# PCB_eLock_G592_J1.net
KiCad netlist of a schematic drawn in EAGLE
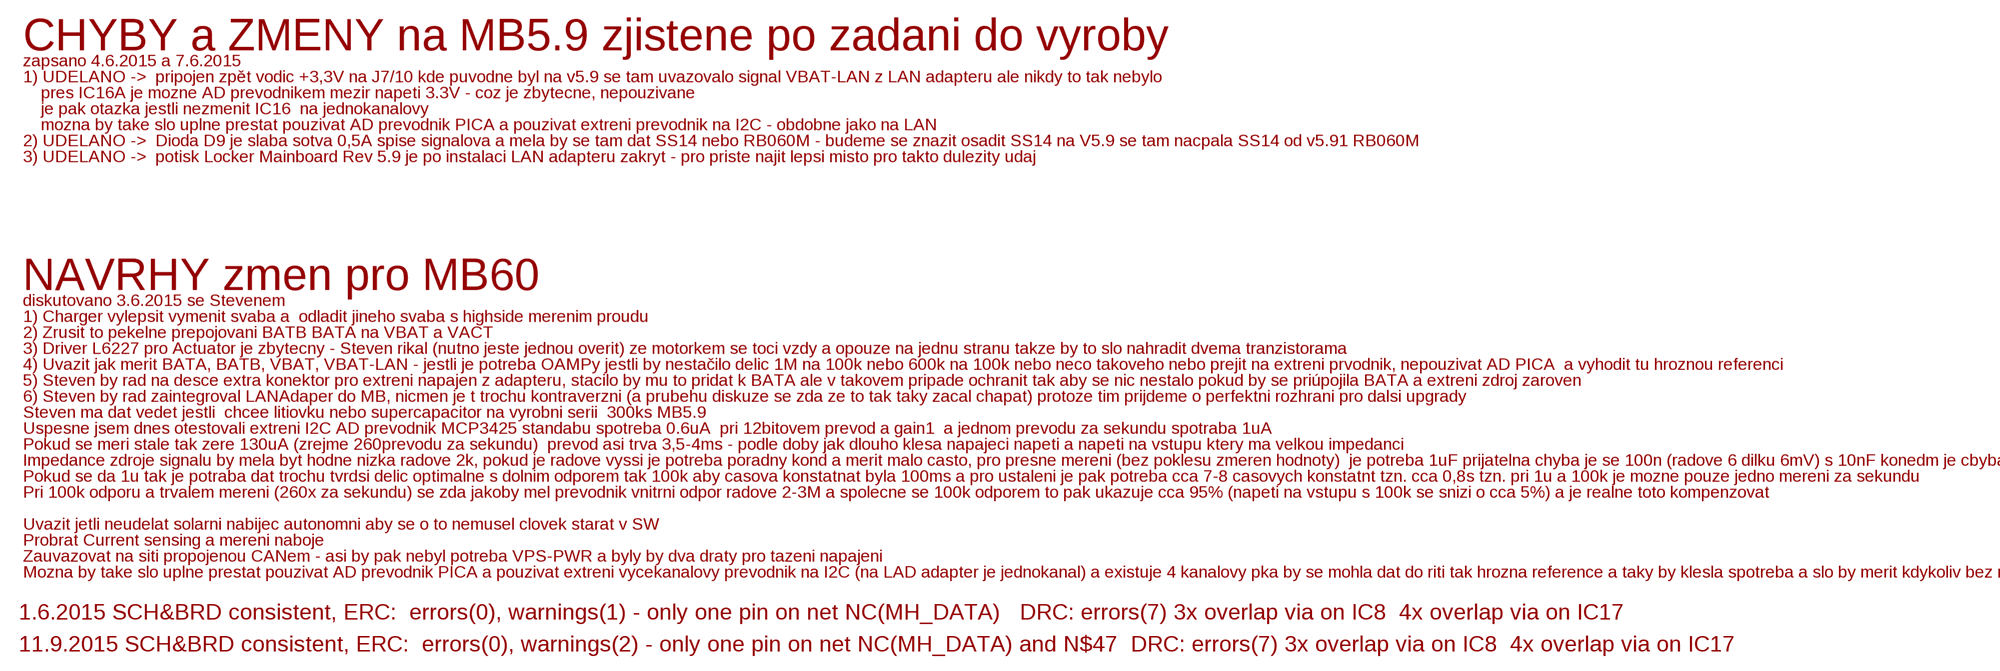
[diagram p0: schematic, sheet 1, part 1 of 3]
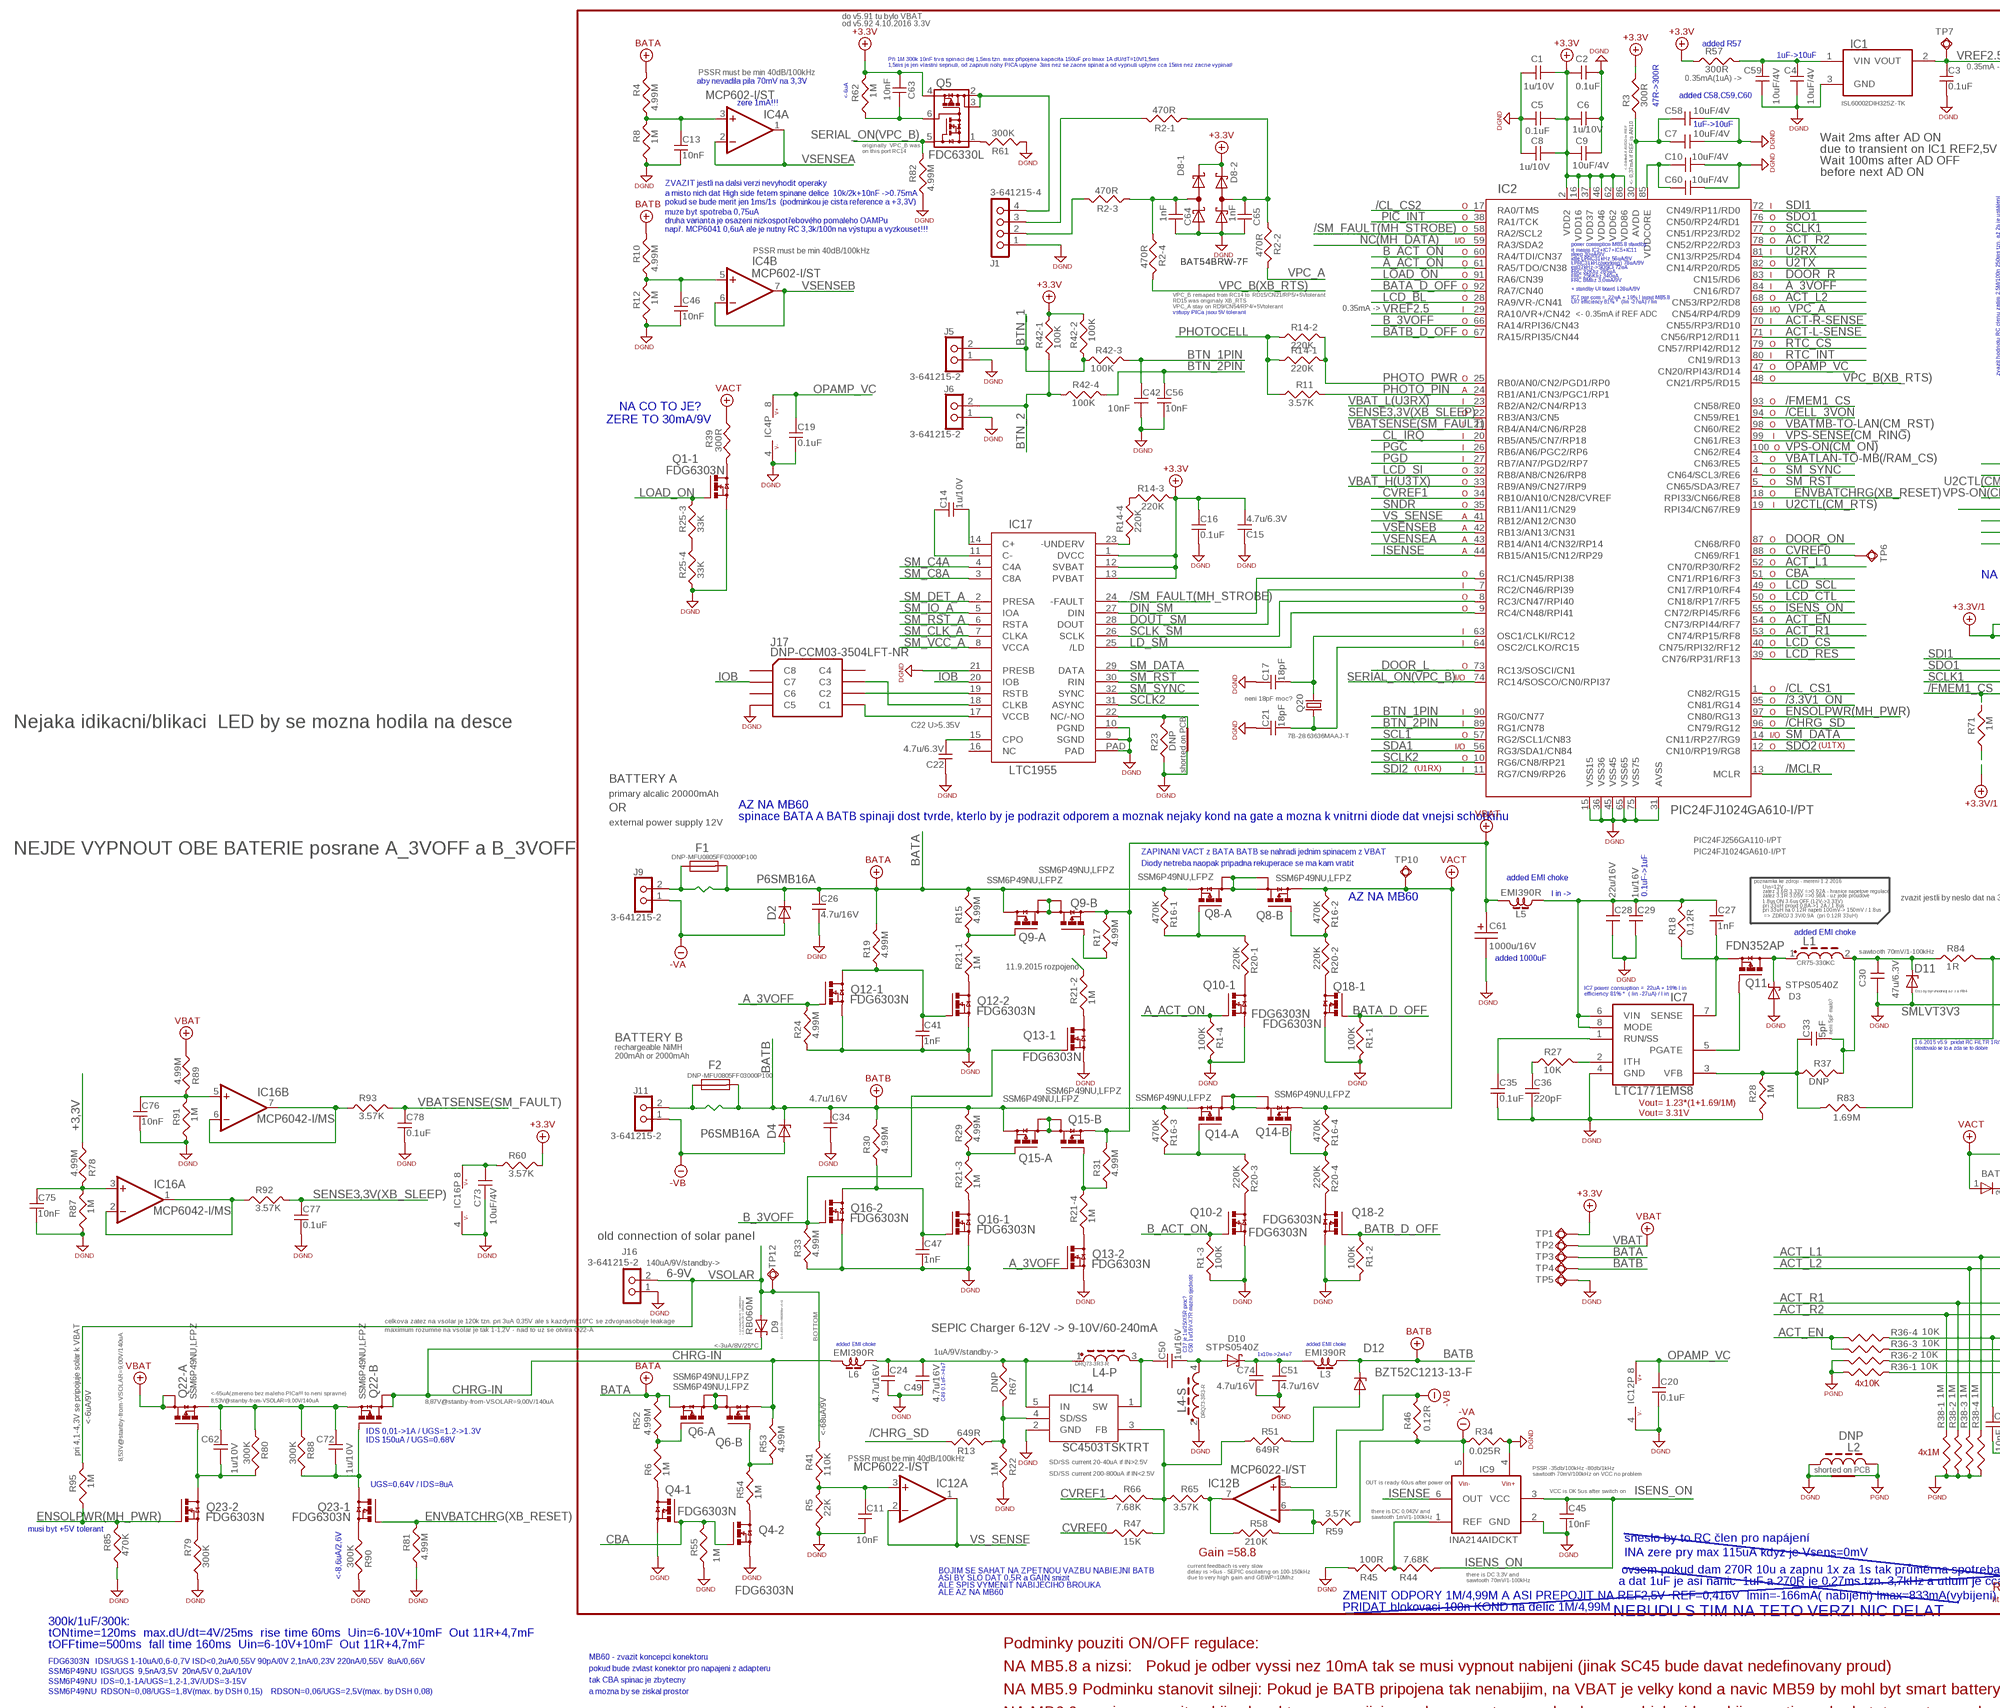
[diagram p1: schematic, sheet 1, part 2 of 3]
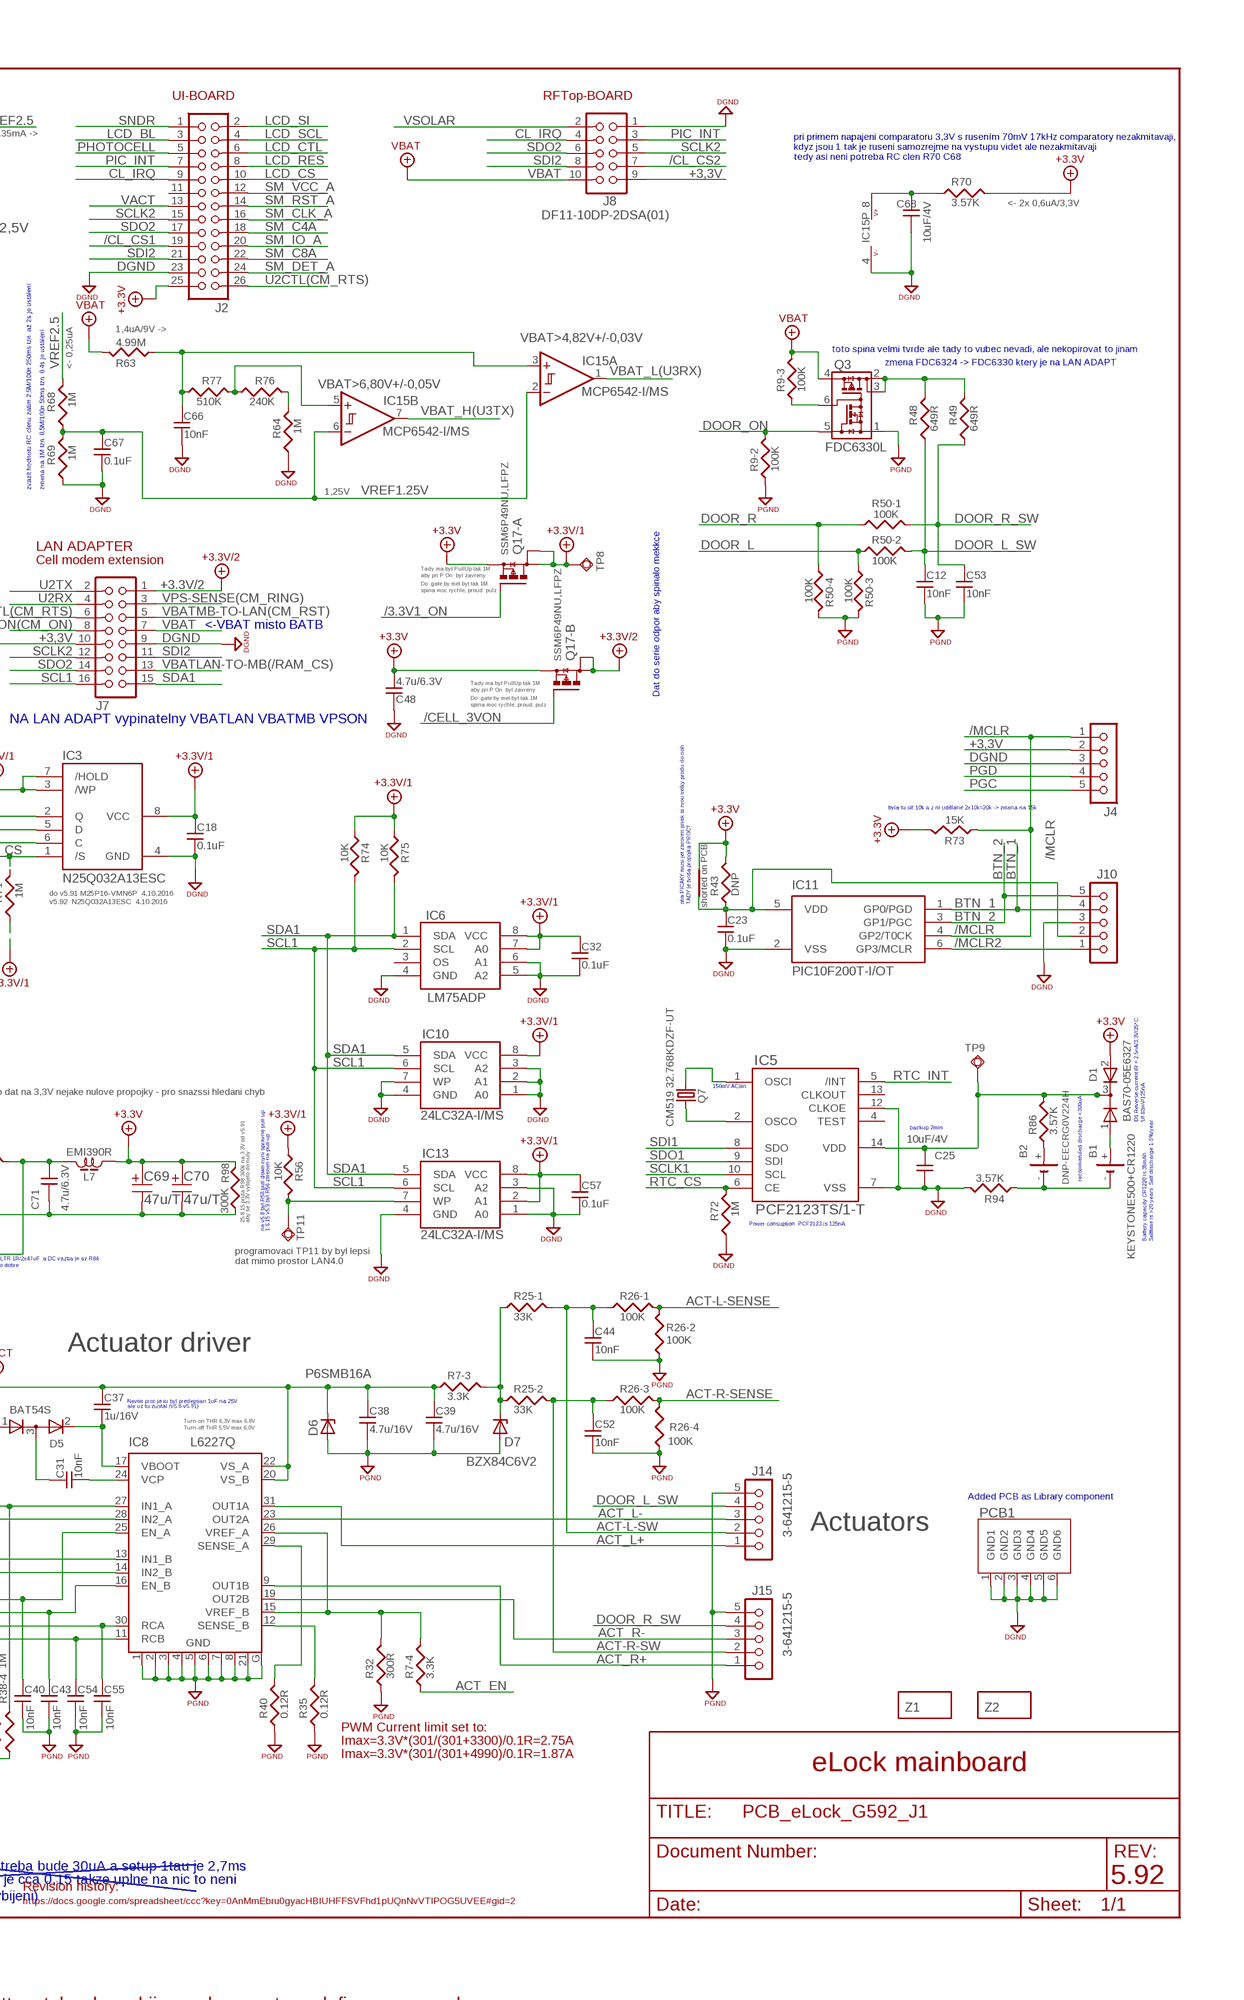
[diagram p2: schematic, sheet 1, part 3 of 3]

(export (version "E")
  (design (tool "Eeschema 10.0.6"))
  (components
    (comp (ref "B1")
      (value "KEYSTONE500+CR1220")
      (footprint "eagle-import:KEYSTONE500")
      (libsource (lib "eagle-import") (part "KEYSTONE500"))
    )
    (comp (ref "B2")
      (value "DNP-EECRG0V224H")
      (footprint "eagle-import:EECRG0V224H")
      (libsource (lib "eagle-import") (part "EECRG0V224H"))
    )
    (comp (ref "C1")
      (value "1u/10V")
      (footprint "eagle-import:0603")
      (libsource (lib "eagle-import") (part "C-0603"))
    )
    (comp (ref "C2")
      (value "0.1uF")
      (footprint "eagle-import:0603")
      (libsource (lib "eagle-import") (part "C-0603"))
    )
    (comp (ref "C3")
      (value "0.1uF")
      (footprint "eagle-import:0603")
      (libsource (lib "eagle-import") (part "C-0603"))
    )
    (comp (ref "C4")
      (value "10uF/4V")
      (footprint "eagle-import:0603")
      (libsource (lib "eagle-import") (part "C-0603"))
    )
    (comp (ref "C5")
      (value "0.1uF")
      (footprint "eagle-import:0603")
      (libsource (lib "eagle-import") (part "C-0603"))
    )
    (comp (ref "C6")
      (value "1u/10V")
      (footprint "eagle-import:0603")
      (libsource (lib "eagle-import") (part "C-0603"))
    )
    (comp (ref "C7")
      (value "10uF/4V")
      (footprint "eagle-import:0603")
      (libsource (lib "eagle-import") (part "C-0603"))
    )
    (comp (ref "C8")
      (value "1u/10V")
      (footprint "eagle-import:0603")
      (libsource (lib "eagle-import") (part "C-0603"))
    )
    (comp (ref "C9")
      (value "10uF/4V")
      (footprint "eagle-import:0603")
      (libsource (lib "eagle-import") (part "C-0603"))
    )
    (comp (ref "C10")
      (value "10uF/4V")
      (footprint "eagle-import:0603")
      (libsource (lib "eagle-import") (part "C-0603"))
    )
    (comp (ref "C11")
      (value "10nF")
      (footprint "eagle-import:0603")
      (libsource (lib "eagle-import") (part "C-0603"))
    )
    (comp (ref "C12")
      (value "10nF")
      (footprint "eagle-import:0603")
      (libsource (lib "eagle-import") (part "C-0603"))
    )
    (comp (ref "C13")
      (value "10nF")
      (footprint "eagle-import:0603")
      (libsource (lib "eagle-import") (part "C-0603"))
    )
    (comp (ref "C14")
      (value "1u/10V")
      (footprint "eagle-import:0603")
      (libsource (lib "eagle-import") (part "C-0603"))
    )
    (comp (ref "C15")
      (value "4.7u/6.3V")
      (footprint "eagle-import:0603")
      (libsource (lib "eagle-import") (part "C-0603"))
    )
    (comp (ref "C16")
      (value "0.1uF")
      (footprint "eagle-import:0603")
      (libsource (lib "eagle-import") (part "C-0603"))
    )
    (comp (ref "C17")
      (value "18pF")
      (footprint "eagle-import:0603")
      (libsource (lib "eagle-import") (part "C-0603"))
    )
    (comp (ref "C18")
      (value "0.1uF")
      (footprint "eagle-import:0603")
      (libsource (lib "eagle-import") (part "C-0603"))
    )
    (comp (ref "C19")
      (value "0.1uF")
      (footprint "eagle-import:0603")
      (libsource (lib "eagle-import") (part "C-0603"))
    )
    (comp (ref "C20")
      (value "0.1uF")
      (footprint "eagle-import:0603")
      (libsource (lib "eagle-import") (part "C-0603"))
    )
    (comp (ref "C21")
      (value "18pF")
      (footprint "eagle-import:0603")
      (libsource (lib "eagle-import") (part "C-0603"))
    )
    (comp (ref "C22")
      (value "4.7u/6.3V")
      (footprint "eagle-import:0603")
      (libsource (lib "eagle-import") (part "C-0603"))
    )
    (comp (ref "C23")
      (value "0.1uF")
      (footprint "eagle-import:0603")
      (libsource (lib "eagle-import") (part "C-0603"))
    )
    (comp (ref "C24")
      (value "4.7u/16V")
      (footprint "eagle-import:0805")
      (libsource (lib "eagle-import") (part "C-0805"))
    )
    (comp (ref "C25")
      (value "10uF/4V")
      (footprint "eagle-import:0603")
      (libsource (lib "eagle-import") (part "C-0603"))
    )
    (comp (ref "C26")
      (value "4.7u/16V")
      (footprint "eagle-import:0805")
      (libsource (lib "eagle-import") (part "C-0805"))
    )
    (comp (ref "C27")
      (value "1nF")
      (footprint "eagle-import:0603")
      (libsource (lib "eagle-import") (part "C-0603"))
    )
    (comp (ref "C28")
      (value "22u/16V")
      (footprint "eagle-import:1210")
      (libsource (lib "eagle-import") (part "C-1210"))
    )
    (comp (ref "C29")
      (value "1u/16V")
      (footprint "eagle-import:0603")
      (libsource (lib "eagle-import") (part "C-0603"))
    )
    (comp (ref "C30")
      (value "47u/6.3V")
      (footprint "eagle-import:1210")
      (libsource (lib "eagle-import") (part "C-1210"))
    )
    (comp (ref "C31")
      (value "10nF")
      (footprint "eagle-import:0603")
      (libsource (lib "eagle-import") (part "C-0603"))
    )
    (comp (ref "C32")
      (value "0.1uF")
      (footprint "eagle-import:0603")
      (libsource (lib "eagle-import") (part "C-0603"))
    )
    (comp (ref "C33")
      (value "5pF")
      (footprint "eagle-import:0603")
      (libsource (lib "eagle-import") (part "C-0603"))
    )
    (comp (ref "C34")
      (value "4.7u/16V")
      (footprint "eagle-import:0805")
      (libsource (lib "eagle-import") (part "C-0805"))
    )
    (comp (ref "C35")
      (value "0.1uF")
      (footprint "eagle-import:0603")
      (libsource (lib "eagle-import") (part "C-0603"))
    )
    (comp (ref "C36")
      (value "220pF")
      (footprint "eagle-import:0603")
      (libsource (lib "eagle-import") (part "C-0603"))
    )
    (comp (ref "C37")
      (value "1u/16V")
      (footprint "eagle-import:0603")
      (libsource (lib "eagle-import") (part "C-0603"))
    )
    (comp (ref "C38")
      (value "4.7u/16V")
      (footprint "eagle-import:0805")
      (libsource (lib "eagle-import") (part "C-0805"))
    )
    (comp (ref "C39")
      (value "4.7u/16V")
      (footprint "eagle-import:0805")
      (libsource (lib "eagle-import") (part "C-0805"))
    )
    (comp (ref "C40")
      (value "10nF")
      (footprint "eagle-import:0603")
      (libsource (lib "eagle-import") (part "C-0603"))
    )
    (comp (ref "C41")
      (value "1nF")
      (footprint "eagle-import:0603")
      (libsource (lib "eagle-import") (part "C-0603"))
    )
    (comp (ref "C42")
      (value "10nF")
      (footprint "eagle-import:0603")
      (libsource (lib "eagle-import") (part "C-0603"))
    )
    (comp (ref "C43")
      (value "10nF")
      (footprint "eagle-import:0603")
      (libsource (lib "eagle-import") (part "C-0603"))
    )
    (comp (ref "C44")
      (value "10nF")
      (footprint "eagle-import:0603")
      (libsource (lib "eagle-import") (part "C-0603"))
    )
    (comp (ref "C45")
      (value "10nF")
      (footprint "eagle-import:0603")
      (libsource (lib "eagle-import") (part "C-0603"))
    )
    (comp (ref "C46")
      (value "10nF")
      (footprint "eagle-import:0603")
      (libsource (lib "eagle-import") (part "C-0603"))
    )
    (comp (ref "C47")
      (value "1nF")
      (footprint "eagle-import:0603")
      (libsource (lib "eagle-import") (part "C-0603"))
    )
    (comp (ref "C48")
      (value "4.7u/6.3V")
      (footprint "eagle-import:0603")
      (libsource (lib "eagle-import") (part "C-0603"))
    )
    (comp (ref "C49")
      (value "4.7u/16V")
      (footprint "eagle-import:0805")
      (libsource (lib "eagle-import") (part "C-0805"))
    )
    (comp (ref "C50")
      (value "1u/16V")
      (footprint "eagle-import:0603")
      (libsource (lib "eagle-import") (part "C-0603"))
    )
    (comp (ref "C51")
      (value "4.7u/16V")
      (footprint "eagle-import:0805")
      (libsource (lib "eagle-import") (part "C-0805"))
    )
    (comp (ref "C52")
      (value "10nF")
      (footprint "eagle-import:0603")
      (libsource (lib "eagle-import") (part "C-0603"))
    )
    (comp (ref "C53")
      (value "10nF")
      (footprint "eagle-import:0603")
      (libsource (lib "eagle-import") (part "C-0603"))
    )
    (comp (ref "C54")
      (value "10nF")
      (footprint "eagle-import:0603")
      (libsource (lib "eagle-import") (part "C-0603"))
    )
    (comp (ref "C55")
      (value "10nF")
      (footprint "eagle-import:0603")
      (libsource (lib "eagle-import") (part "C-0603"))
    )
    (comp (ref "C56")
      (value "10nF")
      (footprint "eagle-import:0603")
      (libsource (lib "eagle-import") (part "C-0603"))
    )
    (comp (ref "C57")
      (value "0.1uF")
      (footprint "eagle-import:0603")
      (libsource (lib "eagle-import") (part "C-0603"))
    )
    (comp (ref "C58")
      (value "10uF/4V")
      (footprint "eagle-import:0603")
      (libsource (lib "eagle-import") (part "C-0603"))
    )
    (comp (ref "C59")
      (value "10uF/4V")
      (footprint "eagle-import:0603")
      (libsource (lib "eagle-import") (part "C-0603"))
    )
    (comp (ref "C60")
      (value "10uF/4V")
      (footprint "eagle-import:0603")
      (libsource (lib "eagle-import") (part "C-0603"))
    )
    (comp (ref "C61")
      (value "1000u/16V")
      (footprint "eagle-import:CE5_13")
      (libsource (lib "eagle-import") (part "CE5/13"))
    )
    (comp (ref "C62")
      (value "1u/10V")
      (footprint "eagle-import:0603")
      (libsource (lib "eagle-import") (part "C-0603"))
    )
    (comp (ref "C63")
      (value "10nF")
      (footprint "eagle-import:0603")
      (libsource (lib "eagle-import") (part "C-0603"))
    )
    (comp (ref "C64")
      (value "1nF")
      (footprint "eagle-import:0603")
      (libsource (lib "eagle-import") (part "C-0603"))
    )
    (comp (ref "C65")
      (value "1nF")
      (footprint "eagle-import:0603")
      (libsource (lib "eagle-import") (part "C-0603"))
    )
    (comp (ref "C66")
      (value "10nF")
      (footprint "eagle-import:0603")
      (libsource (lib "eagle-import") (part "C-0603"))
    )
    (comp (ref "C67")
      (value "0.1uF")
      (footprint "eagle-import:0603")
      (libsource (lib "eagle-import") (part "C-0603"))
    )
    (comp (ref "C68")
      (value "10uF/4V")
      (footprint "eagle-import:0603")
      (libsource (lib "eagle-import") (part "C-0603"))
    )
    (comp (ref "C69")
      (value "47u/T")
      (footprint "eagle-import:CT-C")
      (libsource (lib "eagle-import") (part "CT-C"))
    )
    (comp (ref "C70")
      (value "47u/T")
      (footprint "eagle-import:CT-C")
      (libsource (lib "eagle-import") (part "CT-C"))
    )
    (comp (ref "C71")
      (value "4.7u/6.3V")
      (footprint "eagle-import:0603")
      (libsource (lib "eagle-import") (part "C-0603"))
    )
    (comp (ref "C72")
      (value "1u/10V")
      (footprint "eagle-import:0603")
      (libsource (lib "eagle-import") (part "C-0603"))
    )
    (comp (ref "C73")
      (value "10uF/4V")
      (footprint "eagle-import:0603")
      (libsource (lib "eagle-import") (part "C-0603"))
    )
    (comp (ref "C74")
      (value "4.7u/16V")
      (footprint "eagle-import:0805")
      (libsource (lib "eagle-import") (part "C-0805"))
    )
    (comp (ref "C75")
      (value "10nF")
      (footprint "eagle-import:0603")
      (libsource (lib "eagle-import") (part "C-0603"))
    )
    (comp (ref "C76")
      (value "10nF")
      (footprint "eagle-import:0603")
      (libsource (lib "eagle-import") (part "C-0603"))
    )
    (comp (ref "C77")
      (value "0.1uF")
      (footprint "eagle-import:0603")
      (libsource (lib "eagle-import") (part "C-0603"))
    )
    (comp (ref "C78")
      (value "0.1uF")
      (footprint "eagle-import:0603")
      (libsource (lib "eagle-import") (part "C-0603"))
    )
    (comp (ref "D1")
      (value "BAS70-05E6327")
      (footprint "eagle-import:SOT-23")
      (libsource (lib "eagle-import") (part "BAS70-05E6327"))
    )
    (comp (ref "D2")
      (value "P6SMB16A")
      (footprint "eagle-import:SMB")
      (libsource (lib "eagle-import") (part "P6SMB16A"))
    )
    (comp (ref "D3")
      (value "STPS0540Z")
      (footprint "eagle-import:SOD-123")
      (libsource (lib "eagle-import") (part "STPS0540Z"))
    )
    (comp (ref "D4")
      (value "P6SMB16A")
      (footprint "eagle-import:SMB")
      (libsource (lib "eagle-import") (part "P6SMB16A"))
    )
    (comp (ref "D5")
      (value "BAT54S")
      (footprint "eagle-import:SOT-23")
      (libsource (lib "eagle-import") (part "BAT54S"))
    )
    (comp (ref "D6")
      (value "P6SMB16A")
      (footprint "eagle-import:SMB")
      (libsource (lib "eagle-import") (part "P6SMB16A"))
    )
    (comp (ref "D7")
      (value "BZX84C6V2")
      (footprint "eagle-import:SOT-23")
      (libsource (lib "eagle-import") (part "BZX84C6V2"))
    )
    (comp (ref "D8")
      (value "BAT54BRW-7F")
      (footprint "eagle-import:SOT-363")
      (libsource (lib "eagle-import") (part "BAT54BRW-7F"))
    )
    (comp (ref "D9")
      (value "RB060M")
      (footprint "eagle-import:SOD-123")
      (libsource (lib "eagle-import") (part "MBR0520LT1G"))
    )
    (comp (ref "D10")
      (value "STPS0540Z")
      (footprint "eagle-import:SOD-123")
      (libsource (lib "eagle-import") (part "STPS0540Z"))
    )
    (comp (ref "D11")
      (value "SMLVT3V3")
      (footprint "eagle-import:SMA")
      (libsource (lib "eagle-import") (part "SMLVT3V3"))
    )
    (comp (ref "D12")
      (value "BZT52C1213-13-F")
      (footprint "eagle-import:SOD-123")
      (libsource (lib "eagle-import") (part "BZT52-13-FC1213"))
    )
    (comp (ref "F1")
      (value "DNP-MFU0805FF03000P100")
      (footprint "eagle-import:0805")
      (libsource (lib "eagle-import") (part "MFU0805FF03000P100"))
    )
    (comp (ref "F2")
      (value "DNP-MFU0805FF03000P100")
      (footprint "eagle-import:0805")
      (libsource (lib "eagle-import") (part "MFU0805FF03000P100"))
    )
    (comp (ref "IC1")
      (value "ISL60002DIH325Z-TK")
      (footprint "eagle-import:SOT-23")
      (libsource (lib "eagle-import") (part "ISL60002DIH325Z-TK"))
    )
    (comp (ref "IC2")
      (value "PIC24FJ1024GA610-I/PT")
      (footprint "eagle-import:SQFP-S-12X12-100")
      (libsource (lib "eagle-import") (part "PIC24FJ256GA110-I/PT"))
    )
    (comp (ref "IC3")
      (value "N25Q032A13ESC")
      (footprint "eagle-import:SO-08")
      (libsource (lib "eagle-import") (part "M25P16-VMN6P"))
    )
    (comp (ref "IC4")
      (value "MCP602-I/ST")
      (footprint "eagle-import:TSSOP8")
      (libsource (lib "eagle-import") (part "MCP6022-I/ST"))
    )
    (comp (ref "IC5")
      (value "PCF2123TS/1-T")
      (footprint "eagle-import:TSSOP014")
      (libsource (lib "eagle-import") (part "PCF2123TS/1-T"))
    )
    (comp (ref "IC6")
      (value "LM75ADP")
      (footprint "eagle-import:TSSOP08-3")
      (libsource (lib "eagle-import") (part "LM75ADP"))
    )
    (comp (ref "IC7")
      (value "LTC1771EMS8")
      (footprint "eagle-import:MSOP-08")
      (libsource (lib "eagle-import") (part "LTC1771EMS8"))
    )
    (comp (ref "IC8")
      (value "L6227Q")
      (footprint "eagle-import:SQFP-S-5X5-32")
      (libsource (lib "eagle-import") (part "L6227Q"))
    )
    (comp (ref "IC9")
      (value "INA214AIDCKT")
      (footprint "eagle-import:SC70-6")
      (libsource (lib "eagle-import") (part "INA214AIDCKT"))
    )
    (comp (ref "IC10")
      (value "24LC32A-I/MS")
      (footprint "eagle-import:MSOP-08")
      (libsource (lib "eagle-import") (part "24-I/MS"))
    )
    (comp (ref "IC11")
      (value "PIC10F200T-I/OT")
      (footprint "eagle-import:SOT23-6")
      (libsource (lib "eagle-import") (part "PIC10F200T-I/OT"))
    )
    (comp (ref "IC12")
      (value "MCP6022-I/ST")
      (footprint "eagle-import:TSSOP8")
      (libsource (lib "eagle-import") (part "MCP6022-I/ST"))
    )
    (comp (ref "IC13")
      (value "24LC32A-I/MS")
      (footprint "eagle-import:MSOP-08")
      (libsource (lib "eagle-import") (part "24-I/MS"))
    )
    (comp (ref "IC14")
      (value "SC4503TSKTRT")
      (footprint "eagle-import:SOT23-5")
      (libsource (lib "eagle-import") (part "SC4503TSKTRT"))
    )
    (comp (ref "IC15")
      (value "MCP6542-I/MS")
      (footprint "eagle-import:MSOP-08")
      (libsource (lib "eagle-import") (part "MCP6542-I/MS"))
    )
    (comp (ref "IC16")
      (value "MCP6042-I/MS")
      (footprint "eagle-import:MSOP-08")
      (libsource (lib "eagle-import") (part "MCP6042-I/MS"))
    )
    (comp (ref "IC17")
      (value "LTC1955")
      (footprint "eagle-import:LFCSP_5X5_032")
      (libsource (lib "eagle-import") (part "LTC1955"))
    )
    (comp (ref "J1")
      (value "3-641215-4")
      (footprint "eagle-import:3-641215-4")
      (libsource (lib "eagle-import") (part "3-641215-4"))
    )
    (comp (ref "J2")
      (value "PBC13DABN-2x13pinAu-5.8/2.5/5.8")
      (footprint "eagle-import:MA13-2")
      (libsource (lib "eagle-import") (part "MA13-2"))
    )
    (comp (ref "J4")
      (value "DNP")
      (footprint "eagle-import:MA05-1")
      (libsource (lib "eagle-import") (part "MA05-1"))
    )
    (comp (ref "J5")
      (value "3-641215-2")
      (footprint "eagle-import:3-641215-2")
      (libsource (lib "eagle-import") (part "3-641215-2"))
    )
    (comp (ref "J6")
      (value "3-641215-2")
      (footprint "eagle-import:3-641215-2")
      (libsource (lib "eagle-import") (part "3-641215-2"))
    )
    (comp (ref "J7")
      (value "8x2pin-Au-6/2,5/3")
      (footprint "eagle-import:MA08-2")
      (libsource (lib "eagle-import") (part "MA08-2"))
    )
    (comp (ref "J8")
      (value "DF11-10DP-2DSA(01)")
      (footprint "eagle-import:DF11-10DP-2DSA")
      (libsource (lib "eagle-import") (part "DF11-10DP-2DSA(01)"))
    )
    (comp (ref "J9")
      (value "3-641215-2")
      (footprint "eagle-import:3-641215-2")
      (libsource (lib "eagle-import") (part "3-641215-2"))
    )
    (comp (ref "J10")
      (value "DNP")
      (footprint "eagle-import:MA05-1")
      (libsource (lib "eagle-import") (part "MA05-1"))
    )
    (comp (ref "J11")
      (value "3-641215-2")
      (footprint "eagle-import:3-641215-2")
      (libsource (lib "eagle-import") (part "3-641215-2"))
    )
    (comp (ref "J14")
      (value "3-641215-5")
      (footprint "eagle-import:3-641215-5")
      (libsource (lib "eagle-import") (part "3-641215-5"))
    )
    (comp (ref "J15")
      (value "3-641215-5")
      (footprint "eagle-import:3-641215-5")
      (libsource (lib "eagle-import") (part "3-641215-5"))
    )
    (comp (ref "J16")
      (value "3-641215-2")
      (footprint "eagle-import:3-641215-2")
      (libsource (lib "eagle-import") (part "3-641215-2"))
    )
    (comp (ref "J17")
      (value "DNP-CCM03-3504LFT-NR")
      (footprint "eagle-import:CCM03-3504LFT-NR")
      (libsource (lib "eagle-import") (part "CCM03-3504LFT-NR"))
    )
    (comp (ref "L1")
      (value "CR75-330KC")
      (footprint "eagle-import:CR75")
      (libsource (lib "eagle-import") (part "CR75-330KC"))
    )
    (comp (ref "L2")
      (value "DNP")
      (footprint "eagle-import:0805-0RTOP")
      (libsource (lib "eagle-import") (part "L-0805-0R"))
    )
    (comp (ref "L3")
      (value "EMI390R")
      (footprint "eagle-import:1206")
      (libsource (lib "eagle-import") (part "L-1206E"))
    )
    (comp (ref "L4")
      (value "DRQ73-3R3-R")
      (footprint "eagle-import:DRQ73")
      (libsource (lib "eagle-import") (part "DRQ73-100-R"))
    )
    (comp (ref "L5")
      (value "EMI390R")
      (footprint "eagle-import:1206")
      (libsource (lib "eagle-import") (part "L-1206E"))
    )
    (comp (ref "L6")
      (value "EMI390R")
      (footprint "eagle-import:1206")
      (libsource (lib "eagle-import") (part "L-1206E"))
    )
    (comp (ref "L7")
      (value "EMI390R")
      (footprint "eagle-import:1206")
      (libsource (lib "eagle-import") (part "L-1206E"))
    )
    (comp (ref "PCB1")
      (value "PCB-MB59")
      (footprint "eagle-import:PCB-MB59")
      (libsource (lib "eagle-import") (part "PCB-MB59"))
    )
    (comp (ref "Q1")
      (value "FDG6303N")
      (footprint "eagle-import:SC70-6")
      (libsource (lib "eagle-import") (part "FDG6303N"))
    )
    (comp (ref "Q3")
      (value "FDC6330L")
      (footprint "eagle-import:SSOT-6")
      (libsource (lib "eagle-import") (part "FDC6324L"))
    )
    (comp (ref "Q4")
      (value "FDG6303N")
      (footprint "eagle-import:SC70-6")
      (libsource (lib "eagle-import") (part "FDG6303N"))
    )
    (comp (ref "Q5")
      (value "FDC6330L")
      (footprint "eagle-import:SSOT-6")
      (libsource (lib "eagle-import") (part "FDC6324L"))
    )
    (comp (ref "Q6")
      (value "SSM6P49NU,LFPZ")
      (footprint "eagle-import:MICRO_FET")
      (libsource (lib "eagle-import") (part "SSM6P49PZNU,LF"))
    )
    (comp (ref "Q7")
      (value "CM519 32.768KDZF-UT")
      (footprint "eagle-import:CM519")
      (libsource (lib "eagle-import") (part "CM519"))
    )
    (comp (ref "Q8")
      (value "SSM6P49NU,LFPZ")
      (footprint "eagle-import:MICRO_FET")
      (libsource (lib "eagle-import") (part "SSM6P49PZNU,LF"))
    )
    (comp (ref "Q9")
      (value "SSM6P49NU,LFPZ")
      (footprint "eagle-import:MICRO_FET")
      (libsource (lib "eagle-import") (part "SSM6P49PZNU,LF"))
    )
    (comp (ref "Q10")
      (value "FDG6303N")
      (footprint "eagle-import:SC70-6")
      (libsource (lib "eagle-import") (part "FDG6303N"))
    )
    (comp (ref "Q11")
      (value "FDN352AP")
      (footprint "eagle-import:SOT-23")
      (libsource (lib "eagle-import") (part "FDN352AP"))
    )
    (comp (ref "Q12")
      (value "FDG6303N")
      (footprint "eagle-import:SC70-6")
      (libsource (lib "eagle-import") (part "FDG6303N"))
    )
    (comp (ref "Q13")
      (value "FDG6303N")
      (footprint "eagle-import:SC70-6")
      (libsource (lib "eagle-import") (part "FDG6303N"))
    )
    (comp (ref "Q14")
      (value "SSM6P49NU,LFPZ")
      (footprint "eagle-import:MICRO_FET")
      (libsource (lib "eagle-import") (part "SSM6P49PZNU,LF"))
    )
    (comp (ref "Q15")
      (value "SSM6P49NU,LFPZ")
      (footprint "eagle-import:MICRO_FET")
      (libsource (lib "eagle-import") (part "SSM6P49PZNU,LF"))
    )
    (comp (ref "Q16")
      (value "FDG6303N")
      (footprint "eagle-import:SC70-6")
      (libsource (lib "eagle-import") (part "FDG6303N"))
    )
    (comp (ref "Q17")
      (value "SSM6P49NU,LFPZ")
      (footprint "eagle-import:MICRO_FET")
      (libsource (lib "eagle-import") (part "SSM6P49PZNU,LF"))
    )
    (comp (ref "Q18")
      (value "FDG6303N")
      (footprint "eagle-import:SC70-6")
      (libsource (lib "eagle-import") (part "FDG6303N"))
    )
    (comp (ref "Q20")
      (value "7B-28.63636MAAJ-T")
      (footprint "eagle-import:7B")
      (libsource (lib "eagle-import") (part "7B-27.120MAAJ-T"))
    )
    (comp (ref "Q22")
      (value "SSM6P49NU,LFPZ")
      (footprint "eagle-import:MICRO_FET")
      (libsource (lib "eagle-import") (part "SSM6P49PZNU,LF"))
    )
    (comp (ref "Q23")
      (value "FDG6303N")
      (footprint "eagle-import:SC70-6")
      (libsource (lib "eagle-import") (part "FDG6303N"))
    )
    (comp (ref "R1")
      (value "100K")
      (footprint "eagle-import:0603-ARRAY")
      (libsource (lib "eagle-import") (part "EXB-38"))
    )
    (comp (ref "R2")
      (value "470R")
      (footprint "eagle-import:0603-ARRAY")
      (libsource (lib "eagle-import") (part "EXB-38"))
    )
    (comp (ref "R3")
      (value "300R")
      (footprint "eagle-import:0603")
      (libsource (lib "eagle-import") (part "R-0603"))
    )
    (comp (ref "R4")
      (value "4.99M")
      (footprint "eagle-import:0603")
      (libsource (lib "eagle-import") (part "R-0603"))
    )
    (comp (ref "R5")
      (value "22K")
      (footprint "eagle-import:0603")
      (libsource (lib "eagle-import") (part "R-0603"))
    )
    (comp (ref "R6")
      (value "1M")
      (footprint "eagle-import:0603")
      (libsource (lib "eagle-import") (part "R-0603"))
    )
    (comp (ref "R7")
      (value "3.3K")
      (footprint "eagle-import:0603-ARRAY")
      (libsource (lib "eagle-import") (part "EXB-38"))
    )
    (comp (ref "R8")
      (value "1M")
      (footprint "eagle-import:0603")
      (libsource (lib "eagle-import") (part "R-0603"))
    )
    (comp (ref "R9")
      (value "100K")
      (footprint "eagle-import:0603-ARRAY")
      (libsource (lib "eagle-import") (part "EXB-38"))
    )
    (comp (ref "R10")
      (value "4.99M")
      (footprint "eagle-import:0603")
      (libsource (lib "eagle-import") (part "R-0603"))
    )
    (comp (ref "R11")
      (value "3.57K")
      (footprint "eagle-import:0603")
      (libsource (lib "eagle-import") (part "R-0603"))
    )
    (comp (ref "R12")
      (value "1M")
      (footprint "eagle-import:0603")
      (libsource (lib "eagle-import") (part "R-0603"))
    )
    (comp (ref "R13")
      (value "649R")
      (footprint "eagle-import:0603")
      (libsource (lib "eagle-import") (part "R-0603"))
    )
    (comp (ref "R14")
      (value "220K")
      (footprint "eagle-import:0603-ARRAY")
      (libsource (lib "eagle-import") (part "EXB-38"))
    )
    (comp (ref "R15")
      (value "4.99M")
      (footprint "eagle-import:0603")
      (libsource (lib "eagle-import") (part "R-0603"))
    )
    (comp (ref "R16")
      (value "470K")
      (footprint "eagle-import:0603-ARRAY")
      (libsource (lib "eagle-import") (part "EXB-38"))
    )
    (comp (ref "R17")
      (value "4.99M")
      (footprint "eagle-import:0603")
      (libsource (lib "eagle-import") (part "R-0603"))
    )
    (comp (ref "R18")
      (value "0.12R")
      (footprint "eagle-import:0805")
      (libsource (lib "eagle-import") (part "R-0805"))
    )
    (comp (ref "R19")
      (value "4.99M")
      (footprint "eagle-import:0603")
      (libsource (lib "eagle-import") (part "R-0603"))
    )
    (comp (ref "R20")
      (value "220K")
      (footprint "eagle-import:0603-ARRAY")
      (libsource (lib "eagle-import") (part "EXB-38"))
    )
    (comp (ref "R21")
      (value "1M")
      (footprint "eagle-import:0603-ARRAY")
      (libsource (lib "eagle-import") (part "EXB-38"))
    )
    (comp (ref "R22")
      (value "1M")
      (footprint "eagle-import:0603")
      (libsource (lib "eagle-import") (part "R-0603"))
    )
    (comp (ref "R23")
      (value "DNP")
      (footprint "eagle-import:0603-0RTOP")
      (libsource (lib "eagle-import") (part "R-0603-0RTOP"))
    )
    (comp (ref "R24")
      (value "4.99M")
      (footprint "eagle-import:0603")
      (libsource (lib "eagle-import") (part "R-0603"))
    )
    (comp (ref "R25")
      (value "33K")
      (footprint "eagle-import:0603-ARRAY")
      (libsource (lib "eagle-import") (part "EXB-38"))
    )
    (comp (ref "R26")
      (value "100K")
      (footprint "eagle-import:0603-ARRAY")
      (libsource (lib "eagle-import") (part "EXB-38"))
    )
    (comp (ref "R27")
      (value "10K")
      (footprint "eagle-import:0603")
      (libsource (lib "eagle-import") (part "R-0603"))
    )
    (comp (ref "R28")
      (value "1M")
      (footprint "eagle-import:0603")
      (libsource (lib "eagle-import") (part "R-0603"))
    )
    (comp (ref "R29")
      (value "4.99M")
      (footprint "eagle-import:0603")
      (libsource (lib "eagle-import") (part "R-0603"))
    )
    (comp (ref "R30")
      (value "4.99M")
      (footprint "eagle-import:0603")
      (libsource (lib "eagle-import") (part "R-0603"))
    )
    (comp (ref "R31")
      (value "4.99M")
      (footprint "eagle-import:0603")
      (libsource (lib "eagle-import") (part "R-0603"))
    )
    (comp (ref "R32")
      (value "300R")
      (footprint "eagle-import:0603")
      (libsource (lib "eagle-import") (part "R-0603"))
    )
    (comp (ref "R33")
      (value "4.99M")
      (footprint "eagle-import:0603")
      (libsource (lib "eagle-import") (part "R-0603"))
    )
    (comp (ref "R34")
      (value "0.025R")
      (footprint "eagle-import:0805")
      (libsource (lib "eagle-import") (part "R-0805"))
    )
    (comp (ref "R35")
      (value "0.12R")
      (footprint "eagle-import:0805")
      (libsource (lib "eagle-import") (part "R-0805"))
    )
    (comp (ref "R36")
      (value "10K")
      (footprint "eagle-import:0603-ARRAY")
      (libsource (lib "eagle-import") (part "EXB-38"))
    )
    (comp (ref "R37")
      (value "DNP")
      (footprint "eagle-import:0603")
      (libsource (lib "eagle-import") (part "R-0603"))
    )
    (comp (ref "R38")
      (value "1M")
      (footprint "eagle-import:0603-ARRAY")
      (libsource (lib "eagle-import") (part "EXB-38"))
    )
    (comp (ref "R39")
      (value "300R")
      (footprint "eagle-import:0603")
      (libsource (lib "eagle-import") (part "R-0603"))
    )
    (comp (ref "R40")
      (value "0.12R")
      (footprint "eagle-import:0805")
      (libsource (lib "eagle-import") (part "R-0805"))
    )
    (comp (ref "R41")
      (value "110K")
      (footprint "eagle-import:0603")
      (libsource (lib "eagle-import") (part "R-0603"))
    )
    (comp (ref "R42")
      (value "100K")
      (footprint "eagle-import:0603-ARRAY")
      (libsource (lib "eagle-import") (part "EXB-38"))
    )
    (comp (ref "R43")
      (value "DNP")
      (footprint "eagle-import:0603-0RTOP")
      (libsource (lib "eagle-import") (part "R-0603-0RTOP"))
    )
    (comp (ref "R44")
      (value "7.68K")
      (footprint "eagle-import:0603")
      (libsource (lib "eagle-import") (part "R-0603"))
    )
    (comp (ref "R45")
      (value "100R")
      (footprint "eagle-import:0603")
      (libsource (lib "eagle-import") (part "R-0603"))
    )
    (comp (ref "R46")
      (value "0.12R")
      (footprint "eagle-import:0805")
      (libsource (lib "eagle-import") (part "R-0805"))
    )
    (comp (ref "R47")
      (value "15K")
      (footprint "eagle-import:0603")
      (libsource (lib "eagle-import") (part "R-0603"))
    )
    (comp (ref "R48")
      (value "649R")
      (footprint "eagle-import:0603")
      (libsource (lib "eagle-import") (part "R-0603"))
    )
    (comp (ref "R49")
      (value "649R")
      (footprint "eagle-import:0603")
      (libsource (lib "eagle-import") (part "R-0603"))
    )
    (comp (ref "R50")
      (value "100K")
      (footprint "eagle-import:0603-ARRAY")
      (libsource (lib "eagle-import") (part "EXB-38"))
    )
    (comp (ref "R51")
      (value "649R")
      (footprint "eagle-import:0603")
      (libsource (lib "eagle-import") (part "R-0603"))
    )
    (comp (ref "R52")
      (value "4.99M")
      (footprint "eagle-import:0603")
      (libsource (lib "eagle-import") (part "R-0603"))
    )
    (comp (ref "R53")
      (value "4.99M")
      (footprint "eagle-import:0603")
      (libsource (lib "eagle-import") (part "R-0603"))
    )
    (comp (ref "R54")
      (value "1M")
      (footprint "eagle-import:0603")
      (libsource (lib "eagle-import") (part "R-0603"))
    )
    (comp (ref "R55")
      (value "1M")
      (footprint "eagle-import:0603")
      (libsource (lib "eagle-import") (part "R-0603"))
    )
    (comp (ref "R56")
      (value "10K")
      (footprint "eagle-import:0603")
      (libsource (lib "eagle-import") (part "R-0603"))
    )
    (comp (ref "R57")
      (value "300R")
      (footprint "eagle-import:0603")
      (libsource (lib "eagle-import") (part "R-0603"))
    )
    (comp (ref "R58")
      (value "210K")
      (footprint "eagle-import:0603")
      (libsource (lib "eagle-import") (part "R-0603"))
    )
    (comp (ref "R59")
      (value "3.57K")
      (footprint "eagle-import:0603")
      (libsource (lib "eagle-import") (part "R-0603"))
    )
    (comp (ref "R60")
      (value "3.57K")
      (footprint "eagle-import:0603")
      (libsource (lib "eagle-import") (part "R-0603"))
    )
    (comp (ref "R61")
      (value "300K")
      (footprint "eagle-import:0603")
      (libsource (lib "eagle-import") (part "R-0603"))
    )
    (comp (ref "R62")
      (value "1M")
      (footprint "eagle-import:0603")
      (libsource (lib "eagle-import") (part "R-0603"))
    )
    (comp (ref "R63")
      (value "4.99M")
      (footprint "eagle-import:0603")
      (libsource (lib "eagle-import") (part "R-0603"))
    )
    (comp (ref "R64")
      (value "1M")
      (footprint "eagle-import:0603")
      (libsource (lib "eagle-import") (part "R-0603"))
    )
    (comp (ref "R65")
      (value "3.57K")
      (footprint "eagle-import:0603")
      (libsource (lib "eagle-import") (part "R-0603"))
    )
    (comp (ref "R66")
      (value "7.68K")
      (footprint "eagle-import:0603")
      (libsource (lib "eagle-import") (part "R-0603"))
    )
    (comp (ref "R67")
      (value "DNP")
      (footprint "eagle-import:0603")
      (libsource (lib "eagle-import") (part "R-0603"))
    )
    (comp (ref "R68")
      (value "1M")
      (footprint "eagle-import:0603")
      (libsource (lib "eagle-import") (part "R-0603"))
    )
    (comp (ref "R69")
      (value "1M")
      (footprint "eagle-import:0603")
      (libsource (lib "eagle-import") (part "R-0603"))
    )
    (comp (ref "R70")
      (value "3.57K")
      (footprint "eagle-import:0603")
      (libsource (lib "eagle-import") (part "R-0603"))
    )
    (comp (ref "R71")
      (value "1M")
      (footprint "eagle-import:0603")
      (libsource (lib "eagle-import") (part "R-0603"))
    )
    (comp (ref "R72")
      (value "1M")
      (footprint "eagle-import:0603")
      (libsource (lib "eagle-import") (part "R-0603"))
    )
    (comp (ref "R73")
      (value "15K")
      (footprint "eagle-import:0603")
      (libsource (lib "eagle-import") (part "R-0603"))
    )
    (comp (ref "R74")
      (value "10K")
      (footprint "eagle-import:0603")
      (libsource (lib "eagle-import") (part "R-0603"))
    )
    (comp (ref "R75")
      (value "10K")
      (footprint "eagle-import:0603")
      (libsource (lib "eagle-import") (part "R-0603"))
    )
    (comp (ref "R76")
      (value "240K")
      (footprint "eagle-import:0603")
      (libsource (lib "eagle-import") (part "R-0603"))
    )
    (comp (ref "R77")
      (value "510K")
      (footprint "eagle-import:0603")
      (libsource (lib "eagle-import") (part "R-0603"))
    )
    (comp (ref "R78")
      (value "4.99M")
      (footprint "eagle-import:0603")
      (libsource (lib "eagle-import") (part "R-0603"))
    )
    (comp (ref "R79")
      (value "300K")
      (footprint "eagle-import:0603")
      (libsource (lib "eagle-import") (part "R-0603"))
    )
    (comp (ref "R80")
      (value "300K")
      (footprint "eagle-import:0603")
      (libsource (lib "eagle-import") (part "R-0603"))
    )
    (comp (ref "R81")
      (value "4.99M")
      (footprint "eagle-import:0603")
      (libsource (lib "eagle-import") (part "R-0603"))
    )
    (comp (ref "R82")
      (value "4.99M")
      (footprint "eagle-import:0603")
      (libsource (lib "eagle-import") (part "R-0603"))
    )
    (comp (ref "R83")
      (value "1.69M")
      (footprint "eagle-import:0603")
      (libsource (lib "eagle-import") (part "R-0603"))
    )
    (comp (ref "R84")
      (value "1R")
      (footprint "eagle-import:0805")
      (libsource (lib "eagle-import") (part "R-0805"))
    )
    (comp (ref "R85")
      (value "470K")
      (footprint "eagle-import:0603")
      (libsource (lib "eagle-import") (part "R-0603"))
    )
    (comp (ref "R86")
      (value "3.57K")
      (footprint "eagle-import:0603")
      (libsource (lib "eagle-import") (part "R-0603"))
    )
    (comp (ref "R87")
      (value "1M")
      (footprint "eagle-import:0603")
      (libsource (lib "eagle-import") (part "R-0603"))
    )
    (comp (ref "R88")
      (value "300K")
      (footprint "eagle-import:0603")
      (libsource (lib "eagle-import") (part "R-0603"))
    )
    (comp (ref "R89")
      (value "4.99M")
      (footprint "eagle-import:0603")
      (libsource (lib "eagle-import") (part "R-0603"))
    )
    (comp (ref "R90")
      (value "300K")
      (footprint "eagle-import:0603")
      (libsource (lib "eagle-import") (part "R-0603"))
    )
    (comp (ref "R91")
      (value "1M")
      (footprint "eagle-import:0603")
      (libsource (lib "eagle-import") (part "R-0603"))
    )
    (comp (ref "R92")
      (value "3.57K")
      (footprint "eagle-import:0603")
      (libsource (lib "eagle-import") (part "R-0603"))
    )
    (comp (ref "R93")
      (value "3.57K")
      (footprint "eagle-import:0603")
      (libsource (lib "eagle-import") (part "R-0603"))
    )
    (comp (ref "R94")
      (value "3.57K")
      (footprint "eagle-import:0603")
      (libsource (lib "eagle-import") (part "R-0603"))
    )
    (comp (ref "R95")
      (value "1M")
      (footprint "eagle-import:0603")
      (libsource (lib "eagle-import") (part "R-0603"))
    )
    (comp (ref "R98")
      (value "300K")
      (footprint "eagle-import:0603")
      (libsource (lib "eagle-import") (part "R-0603"))
    )
    (comp (ref "TP1")
      (value "DNP-TestPoint")
      (footprint "eagle-import:SMD_ROUND_1MM")
      (libsource (lib "eagle-import") (part "ROUND_SMD1MM"))
    )
    (comp (ref "TP2")
      (value "DNP-TestPoint")
      (footprint "eagle-import:SMD_ROUND_1MM")
      (libsource (lib "eagle-import") (part "ROUND_SMD1MM"))
    )
    (comp (ref "TP3")
      (value "DNP-TestPoint")
      (footprint "eagle-import:SMD_ROUND_1MM")
      (libsource (lib "eagle-import") (part "DNP-TESTPOINT1MM"))
    )
    (comp (ref "TP4")
      (value "DNP-TestPoint")
      (footprint "eagle-import:SMD_ROUND_1MM")
      (libsource (lib "eagle-import") (part "DNP-TESTPOINT1MM"))
    )
    (comp (ref "TP5")
      (value "DNP-TestPoint")
      (footprint "eagle-import:SMD_ROUND_1MM")
      (libsource (lib "eagle-import") (part "ROUND_SMD1MM"))
    )
    (comp (ref "TP6")
      (value "DNP-TestPoint")
      (footprint "eagle-import:SMD_ROUND_1MM")
      (libsource (lib "eagle-import") (part "ROUND_SMD1MM"))
    )
    (comp (ref "TP7")
      (value "DNP-TestPoint")
      (footprint "eagle-import:SMD_ROUND_1MM")
      (libsource (lib "eagle-import") (part "ROUND_SMD1MM"))
    )
    (comp (ref "TP8")
      (value "DNP-TestPoint")
      (footprint "eagle-import:SMD_ROUND_1MM")
      (libsource (lib "eagle-import") (part "ROUND_SMD1MM"))
    )
    (comp (ref "TP9")
      (value "DNP-TestPoint")
      (footprint "eagle-import:SMD_ROUND_1MM")
      (libsource (lib "eagle-import") (part "ROUND_SMD1MM"))
    )
    (comp (ref "TP10")
      (value "DNP-TestPoint")
      (footprint "eagle-import:SMD_ROUND_1MM")
      (libsource (lib "eagle-import") (part "ROUND_SMD1MM"))
    )
    (comp (ref "TP11")
      (value "DNP-TestPoint")
      (footprint "eagle-import:SMD_ROUND_1MM")
      (libsource (lib "eagle-import") (part "ROUND_SMD1MM"))
    )
    (comp (ref "TP12")
      (value "DNP-TestPoint")
      (footprint "eagle-import:SMD_ROUND_1MM")
      (libsource (lib "eagle-import") (part "ROUND_SMD1MM"))
    )
    (comp (ref "Z1")
      (value "DNP-FiducialMark")
      (footprint "eagle-import:REF")
      (libsource (lib "eagle-import") (part "REF"))
    )
    (comp (ref "Z2")
      (value "DNP-FiducialMark")
      (footprint "eagle-import:REF")
      (libsource (lib "eagle-import") (part "REF"))
    )
  )
  (nets
    (net (code "1") (name "+3.3V") (class "Default")
      (node (ref "C1") (pin "1") (pinfunction "1_1") (pintype "passive"))
      (node (ref "C15") (pin "2") (pinfunction "2_2") (pintype "passive"))
      (node (ref "C16") (pin "1") (pinfunction "1_1") (pintype "passive"))
      (node (ref "C2") (pin "1") (pinfunction "1_1") (pintype "passive"))
      (node (ref "C48") (pin "2") (pinfunction "2_2") (pintype "passive"))
      (node (ref "C5") (pin "1") (pinfunction "1_1") (pintype "passive"))
      (node (ref "C6") (pin "1") (pinfunction "1_1") (pintype "passive"))
      (node (ref "C63") (pin "1") (pinfunction "1_1") (pintype "passive"))
      (node (ref "C69") (pin "+") (pinfunction "+_+") (pintype "passive"))
      (node (ref "C70") (pin "+") (pinfunction "+_+") (pintype "passive"))
      (node (ref "C8") (pin "1") (pinfunction "1_1") (pintype "passive"))
      (node (ref "C9") (pin "1") (pinfunction "1_1") (pintype "passive"))
      (node (ref "D1") (pin "2") (pinfunction "A2_2") (pintype "passive"))
      (node (ref "D8") (pin "4") (pinfunction "K_4") (pintype "passive"))
      (node (ref "D8") (pin "5") (pinfunction "K_5") (pintype "passive"))
      (node (ref "IC17") (pin "1") (pinfunction "DVCC_1") (pintype "bidirectional"))
      (node (ref "IC17") (pin "12") (pinfunction "SVBAT_12") (pintype "input"))
      (node (ref "IC17") (pin "13") (pinfunction "PVBAT_13") (pintype "input"))
      (node (ref "IC2") (pin "16") (pinfunction "VDD16_16") (pintype "input"))
      (node (ref "IC2") (pin "2") (pinfunction "VDD2_2") (pintype "input"))
      (node (ref "IC2") (pin "37") (pinfunction "VDD37_37") (pintype "input"))
      (node (ref "IC2") (pin "46") (pinfunction "VDD46_46") (pintype "input"))
      (node (ref "IC2") (pin "62") (pinfunction "VDD62_62") (pintype "input"))
      (node (ref "IC2") (pin "86") (pinfunction "VDD86_86") (pintype "input"))
      (node (ref "J2") (pin "25") (pinfunction "25_25") (pintype "passive"))
      (node (ref "J4") (pin "2") (pinfunction "2_2") (pintype "passive"))
      (node (ref "J7") (pin "10") (pinfunction "10_10") (pintype "passive"))
      (node (ref "J8") (pin "9") (pinfunction "9_9") (pintype "passive"))
      (node (ref "L7") (pin "2") (pinfunction "2_2") (pintype "passive"))
      (node (ref "Q17") (pin "1") (pinfunction "S_1") (pintype "passive"))
      (node (ref "Q17") (pin "4") (pinfunction "S_4") (pintype "passive"))
      (node (ref "Q5") (pin "4") (pinfunction "Q2S_4") (pintype "bidirectional"))
      (node (ref "R14") (pin "3") (pinfunction "1_3") (pintype "passive"))
      (node (ref "R3") (pin "2") (pinfunction "2_2") (pintype "passive"))
      (node (ref "R42") (pin "7") (pinfunction "2_7") (pintype "passive"))
      (node (ref "R42") (pin "8") (pinfunction "2_8") (pintype "passive"))
      (node (ref "R43") (pin "2") (pinfunction "2_2") (pintype "passive"))
      (node (ref "R57") (pin "1") (pinfunction "1_1") (pintype "passive"))
      (node (ref "R60") (pin "2") (pinfunction "2_2") (pintype "passive"))
      (node (ref "R62") (pin "1") (pinfunction "1_1") (pintype "passive"))
      (node (ref "R70") (pin "2") (pinfunction "2_2") (pintype "passive"))
      (node (ref "R73") (pin "2") (pinfunction "2_2") (pintype "passive"))
      (node (ref "R78") (pin "2") (pinfunction "2_2") (pintype "passive"))
      (node (ref "R98") (pin "1") (pinfunction "1_1") (pintype "passive"))
      (node (ref "TP1") (pin "P$1") (pinfunction "TP_P$1") (pintype "passive"))
    )
    (net (code "2") (name "+3.3V{slash}1") (class "Default")
      (node (ref "C18") (pin "1") (pinfunction "1_1") (pintype "passive"))
      (node (ref "C32") (pin "1") (pinfunction "1_1") (pintype "passive"))
      (node (ref "C57") (pin "1") (pinfunction "1_1") (pintype "passive"))
      (node (ref "IC10") (pin "8") (pinfunction "VCC_8") (pintype "input"))
      (node (ref "IC13") (pin "2") (pinfunction "A1_2") (pintype "input"))
      (node (ref "IC13") (pin "8") (pinfunction "VCC_8") (pintype "input"))
      (node (ref "IC3") (pin "3") (pinfunction "/WP_3") (pintype "input"))
      (node (ref "IC3") (pin "7") (pinfunction "/HOLD_7") (pintype "input"))
      (node (ref "IC3") (pin "8") (pinfunction "VCC_8") (pintype "input"))
      (node (ref "IC6") (pin "7") (pinfunction "A0_7") (pintype "input"))
      (node (ref "IC6") (pin "8") (pinfunction "VCC_8") (pintype "input"))
      (node (ref "Q17") (pin "6") (pinfunction "D_6") (pintype "passive"))
      (node (ref "Q17") (pin "P1") (pinfunction "D1_P1") (pintype "passive"))
      (node (ref "R56") (pin "1") (pinfunction "1_1") (pintype "passive"))
      (node (ref "R71") (pin "2") (pinfunction "2_2") (pintype "passive"))
      (node (ref "R74") (pin "1") (pinfunction "1_1") (pintype "passive"))
      (node (ref "R75") (pin "1") (pinfunction "1_1") (pintype "passive"))
      (node (ref "TP8") (pin "P$1") (pinfunction "TP_P$1") (pintype "passive"))
    )
    (net (code "3") (name "+3.3V{slash}2") (class "Default")
      (node (ref "J7") (pin "1") (pinfunction "1_1") (pintype "passive"))
      (node (ref "Q17") (pin "3") (pinfunction "D_3") (pintype "passive"))
      (node (ref "Q17") (pin "P2") (pinfunction "D1_P2") (pintype "passive"))
    )
    (net (code "4") (name "-VA") (class "Default")
      (node (ref "D2") (pin "A") (pinfunction "A_A") (pintype "passive"))
      (node (ref "IC9") (pin "5") (pinfunction "VIN-_5") (pintype "input"))
      (node (ref "J9") (pin "1") (pinfunction "1_1") (pintype "passive"))
      (node (ref "R34") (pin "1") (pinfunction "1_1") (pintype "passive"))
      (node (ref "R46") (pin "1") (pinfunction "1_1") (pintype "passive"))
      (node (ref "R59") (pin "2") (pinfunction "2_2") (pintype "passive"))
    )
    (net (code "5") (name "-VB") (class "Default")
      (node (ref "D4") (pin "A") (pinfunction "A_A") (pintype "passive"))
      (node (ref "IC12") (pin "5") (pinfunction "+IN_5") (pintype "input"))
      (node (ref "J11") (pin "1") (pinfunction "1_1") (pintype "passive"))
      (node (ref "R46") (pin "2") (pinfunction "2_2") (pintype "passive"))
    )
    (net (code "6") (name "/ACT-L-SENSE") (class "Default")
      (node (ref "IC2") (pin "71") (pinfunction "CN56/RP12/RD11_71") (pintype "bidirectional"))
      (node (ref "R26") (pin "7") (pinfunction "2_7") (pintype "passive"))
      (node (ref "R26") (pin "8") (pinfunction "2_8") (pintype "passive"))
    )
    (net (code "7") (name "/ACT-L-SW") (class "Default")
      (node (ref "C44") (pin "1") (pinfunction "1_1") (pintype "passive"))
      (node (ref "J14") (pin "2") (pinfunction "2_2") (pintype "passive"))
      (node (ref "R25") (pin "8") (pinfunction "2_8") (pintype "passive"))
      (node (ref "R26") (pin "1") (pinfunction "1_1") (pintype "passive"))
    )
    (net (code "8") (name "/ACT-R-SENSE") (class "Default")
      (node (ref "IC2") (pin "70") (pinfunction "CN55/RP3/RD10_70") (pintype "bidirectional"))
      (node (ref "R26") (pin "5") (pinfunction "2_5") (pintype "passive"))
      (node (ref "R26") (pin "6") (pinfunction "2_6") (pintype "passive"))
    )
    (net (code "9") (name "/ACT-R-SW") (class "Default")
      (node (ref "C52") (pin "1") (pinfunction "1_1") (pintype "passive"))
      (node (ref "J15") (pin "2") (pinfunction "2_2") (pintype "passive"))
      (node (ref "R25") (pin "7") (pinfunction "2_7") (pintype "passive"))
      (node (ref "R26") (pin "3") (pinfunction "1_3") (pintype "passive"))
    )
    (net (code "10") (name "/ACT_EN") (class "Default")
      (node (ref "IC2") (pin "54") (pinfunction "CN73/RPI44/RF7_54") (pintype "bidirectional"))
      (node (ref "R36") (pin "5") (pinfunction "2_5") (pintype "passive"))
      (node (ref "R36") (pin "6") (pinfunction "2_6") (pintype "passive"))
      (node (ref "R7") (pin "4") (pinfunction "1_4") (pintype "passive"))
    )
    (net (code "11") (name "/ACT_L+") (class "Default")
      (node (ref "IC8") (pin "31") (pinfunction "OUT1A_31") (pintype "output"))
      (node (ref "J14") (pin "1") (pinfunction "1_1") (pintype "passive"))
    )
    (net (code "12") (name "/ACT_L-") (class "Default")
      (node (ref "IC8") (pin "23") (pinfunction "OUT2A_23") (pintype "output"))
      (node (ref "J14") (pin "3") (pinfunction "3_3") (pintype "passive"))
    )
    (net (code "13") (name "/ACT_L1") (class "Default")
      (node (ref "IC2") (pin "52") (pinfunction "CN70/RP30/RF2_52") (pintype "bidirectional"))
      (node (ref "IC8") (pin "27") (pinfunction "IN1_A_27") (pintype "input"))
      (node (ref "R38") (pin "5") (pinfunction "2_5") (pintype "passive"))
    )
    (net (code "14") (name "/ACT_L2") (class "Default")
      (node (ref "IC2") (pin "68") (pinfunction "CN53/RP2/RD8_68") (pintype "bidirectional"))
      (node (ref "IC8") (pin "28") (pinfunction "IN2_A_28") (pintype "input"))
      (node (ref "R38") (pin "6") (pinfunction "2_6") (pintype "passive"))
    )
    (net (code "15") (name "/ACT_R+") (class "Default")
      (node (ref "IC8") (pin "9") (pinfunction "OUT1B_9") (pintype "output"))
      (node (ref "J15") (pin "1") (pinfunction "1_1") (pintype "passive"))
    )
    (net (code "16") (name "/ACT_R-") (class "Default")
      (node (ref "IC8") (pin "19") (pinfunction "OUT2B_19") (pintype "output"))
      (node (ref "J15") (pin "3") (pinfunction "3_3") (pintype "passive"))
    )
    (net (code "17") (name "/ACT_R1") (class "Default")
      (node (ref "IC2") (pin "53") (pinfunction "CN74/RP15/RF8_53") (pintype "bidirectional"))
      (node (ref "IC8") (pin "13") (pinfunction "IN1_B_13") (pintype "input"))
      (node (ref "R38") (pin "7") (pinfunction "2_7") (pintype "passive"))
    )
    (net (code "18") (name "/ACT_R2") (class "Default")
      (node (ref "IC2") (pin "78") (pinfunction "CN52/RP22/RD3_78") (pintype "bidirectional"))
      (node (ref "IC8") (pin "14") (pinfunction "IN2_B_14") (pintype "input"))
      (node (ref "R38") (pin "8") (pinfunction "2_8") (pintype "passive"))
    )
    (net (code "19") (name "/A_3VOFF") (class "Default")
      (node (ref "IC2") (pin "84") (pinfunction "CN16/RD7_84") (pintype "bidirectional"))
      (node (ref "Q12") (pin "2") (pinfunction "G_2") (pintype "passive"))
      (node (ref "Q13") (pin "5") (pinfunction "G_5") (pintype "passive"))
      (node (ref "R24") (pin "2") (pinfunction "2_2") (pintype "passive"))
    )
    (net (code "20") (name "/A_ACT_ON") (class "Default")
      (node (ref "IC2") (pin "61") (pinfunction "RA5/TDO/CN38_61") (pintype "bidirectional"))
      (node (ref "Q10") (pin "2") (pinfunction "G_2") (pintype "passive"))
      (node (ref "R1") (pin "4") (pinfunction "1_4") (pintype "passive"))
    )
    (net (code "21") (name "/BATA_D_OFF") (class "Default")
      (node (ref "IC2") (pin "92") (pinfunction "RA7/CN40_92") (pintype "bidirectional"))
      (node (ref "Q18") (pin "2") (pinfunction "G_2") (pintype "passive"))
      (node (ref "R1") (pin "1") (pinfunction "1_1") (pintype "passive"))
    )
    (net (code "22") (name "/BATB_D_OFF") (class "Default")
      (node (ref "IC2") (pin "67") (pinfunction "RA15/RPI35/CN44_67") (pintype "bidirectional"))
      (node (ref "Q18") (pin "5") (pinfunction "G_5") (pintype "passive"))
      (node (ref "R1") (pin "2") (pinfunction "1_2") (pintype "passive"))
    )
    (net (code "23") (name "/BTN_1") (class "Default")
      (node (ref "IC11") (pin "1") (pinfunction "GP0/PGD_1") (pintype "bidirectional"))
      (node (ref "J10") (pin "4") (pinfunction "4_4") (pintype "passive"))
      (node (ref "J5") (pin "2") (pinfunction "2_2") (pintype "passive"))
      (node (ref "R42") (pin "2") (pinfunction "1_2") (pintype "passive"))
      (node (ref "R42") (pin "3") (pinfunction "1_3") (pintype "passive"))
    )
    (net (code "24") (name "/BTN_1PIN") (class "Default")
      (node (ref "C42") (pin "1") (pinfunction "1_1") (pintype "passive"))
      (node (ref "IC2") (pin "90") (pinfunction "RG0/CN77_90") (pintype "bidirectional"))
      (node (ref "R42") (pin "6") (pinfunction "2_6") (pintype "passive"))
    )
    (net (code "25") (name "/BTN_2") (class "Default")
      (node (ref "IC11") (pin "3") (pinfunction "GP1/PGC_3") (pintype "bidirectional"))
      (node (ref "J10") (pin "5") (pinfunction "5_5") (pintype "passive"))
      (node (ref "J6") (pin "2") (pinfunction "2_2") (pintype "passive"))
      (node (ref "R42") (pin "1") (pinfunction "1_1") (pintype "passive"))
      (node (ref "R42") (pin "4") (pinfunction "1_4") (pintype "passive"))
    )
    (net (code "26") (name "/BTN_2PIN") (class "Default")
      (node (ref "C56") (pin "1") (pinfunction "1_1") (pintype "passive"))
      (node (ref "IC2") (pin "89") (pinfunction "RG1/CN78_89") (pintype "bidirectional"))
      (node (ref "R42") (pin "5") (pinfunction "2_5") (pintype "passive"))
    )
    (net (code "27") (name "/B_3VOFF") (class "Default")
      (node (ref "IC2") (pin "66") (pinfunction "RA14/RPI36/CN43_66") (pintype "bidirectional"))
      (node (ref "Q13") (pin "2") (pinfunction "G_2") (pintype "passive"))
      (node (ref "Q16") (pin "5") (pinfunction "G_5") (pintype "passive"))
      (node (ref "R33") (pin "2") (pinfunction "2_2") (pintype "passive"))
    )
    (net (code "28") (name "/B_ACT_ON") (class "Default")
      (node (ref "IC2") (pin "60") (pinfunction "RA4/TDI/CN37_60") (pintype "bidirectional"))
      (node (ref "Q10") (pin "5") (pinfunction "G_5") (pintype "passive"))
      (node (ref "R1") (pin "6") (pinfunction "2_6") (pintype "passive"))
    )
    (net (code "29") (name "/CBA") (class "Default")
      (node (ref "IC2") (pin "51") (pinfunction "CN71/RP16/RF3_51") (pintype "bidirectional"))
      (node (ref "Q4") (pin "2") (pinfunction "G_2") (pintype "passive"))
      (node (ref "Q4") (pin "5") (pinfunction "G_5") (pintype "passive"))
      (node (ref "R55") (pin "2") (pinfunction "2_2") (pintype "passive"))
    )
    (net (code "30") (name "/CHRG-IN") (class "Default")
      (node (ref "D9") (pin "K") (pinfunction "K_K") (pintype "passive"))
      (node (ref "L6") (pin "1") (pinfunction "1_1") (pintype "passive"))
      (node (ref "Q22") (pin "3") (pinfunction "D_3") (pintype "passive"))
      (node (ref "Q22") (pin "P2") (pinfunction "D1_P2") (pintype "passive"))
      (node (ref "Q6") (pin "4") (pinfunction "S_4") (pintype "passive"))
      (node (ref "R53") (pin "2") (pinfunction "2_2") (pintype "passive"))
    )
    (net (code "31") (name "/CL_IRQ") (class "Default")
      (node (ref "IC2") (pin "20") (pinfunction "RB5/AN5/CN7/RP18_20") (pintype "bidirectional"))
      (node (ref "J2") (pin "9") (pinfunction "9_9") (pintype "passive"))
      (node (ref "J8") (pin "4") (pinfunction "4_4") (pintype "passive"))
    )
    (net (code "32") (name "/CVREF0") (class "Default")
      (node (ref "IC2") (pin "88") (pinfunction "CN69/RF1_88") (pintype "bidirectional"))
      (node (ref "R47") (pin "2") (pinfunction "2_2") (pintype "passive"))
      (node (ref "TP6") (pin "P$1") (pinfunction "TP_P$1") (pintype "passive"))
    )
    (net (code "33") (name "/CVREF1") (class "Default")
      (node (ref "IC2") (pin "34") (pinfunction "RB10/AN10/CN28/CVREF_34") (pintype "bidirectional"))
      (node (ref "R66") (pin "2") (pinfunction "2_2") (pintype "passive"))
    )
    (net (code "34") (name "/DIN_SM") (class "Default")
      (node (ref "IC17") (pin "27") (pinfunction "DIN_27") (pintype "bidirectional"))
      (node (ref "IC2") (pin "6") (pinfunction "RC1/CN45/RPI38_6") (pintype "bidirectional"))
    )
    (net (code "35") (name "/DOOR_L") (class "Default")
      (node (ref "IC2") (pin "73") (pinfunction "RC13/SOSCI/CN1_73") (pintype "bidirectional"))
      (node (ref "R50") (pin "2") (pinfunction "1_2") (pintype "passive"))
      (node (ref "R50") (pin "3") (pinfunction "1_3") (pintype "passive"))
    )
    (net (code "36") (name "/DOOR_L_SW") (class "Default")
      (node (ref "C12") (pin "1") (pinfunction "1_1") (pintype "passive"))
      (node (ref "J14") (pin "4") (pinfunction "4_4") (pintype "passive"))
      (node (ref "R48") (pin "2") (pinfunction "2_2") (pintype "passive"))
      (node (ref "R50") (pin "7") (pinfunction "2_7") (pintype "passive"))
    )
    (net (code "37") (name "/DOOR_ON") (class "Default")
      (node (ref "IC2") (pin "87") (pinfunction "CN68/RF0_87") (pintype "bidirectional"))
      (node (ref "Q3") (pin "5") (pinfunction "Q1G_5") (pintype "input"))
      (node (ref "R9") (pin "7") (pinfunction "2_7") (pintype "passive"))
    )
    (net (code "38") (name "/DOOR_R") (class "Default")
      (node (ref "IC2") (pin "83") (pinfunction "CN15/RD6_83") (pintype "bidirectional"))
      (node (ref "R50") (pin "1") (pinfunction "1_1") (pintype "passive"))
      (node (ref "R50") (pin "4") (pinfunction "1_4") (pintype "passive"))
    )
    (net (code "39") (name "/DOOR_R_SW") (class "Default")
      (node (ref "C53") (pin "1") (pinfunction "1_1") (pintype "passive"))
      (node (ref "J15") (pin "4") (pinfunction "4_4") (pintype "passive"))
      (node (ref "R49") (pin "2") (pinfunction "2_2") (pintype "passive"))
      (node (ref "R50") (pin "8") (pinfunction "2_8") (pintype "passive"))
    )
    (net (code "40") (name "/DOUT_SM") (class "Default")
      (node (ref "IC17") (pin "28") (pinfunction "DOUT_28") (pintype "bidirectional"))
      (node (ref "IC2") (pin "7") (pinfunction "RC2/CN46/RPI39_7") (pintype "bidirectional"))
    )
    (net (code "41") (name "/ENSOLPWR(MH_PWR)") (class "Default")
      (node (ref "IC2") (pin "97") (pinfunction "CN80/RG13_97") (pintype "bidirectional"))
      (node (ref "Q23") (pin "5") (pinfunction "G_5") (pintype "passive"))
      (node (ref "R85") (pin "1") (pinfunction "1_1") (pintype "passive"))
      (node (ref "R95") (pin "2") (pinfunction "2_2") (pintype "passive"))
    )
    (net (code "42") (name "/ENVBATCHRG(XB_RESET)") (class "Default")
      (node (ref "IC2") (pin "18") (pinfunction "RPI33/CN66/RE8_18") (pintype "bidirectional"))
      (node (ref "Q23") (pin "2") (pinfunction "G_2") (pintype "passive"))
      (node (ref "R81") (pin "1") (pinfunction "1_1") (pintype "passive"))
    )
    (net (code "43") (name "/IOB") (class "Default")
      (node (ref "IC17") (pin "20") (pinfunction "IOB_20") (pintype "bidirectional"))
      (node (ref "J17") (pin "C7") (pinfunction "C7_C7") (pintype "bidirectional"))
    )
    (net (code "44") (name "/ISENSE") (class "Default")
      (node (ref "IC2") (pin "44") (pinfunction "RB15/AN15/CN12/RP29_44") (pintype "bidirectional"))
      (node (ref "IC9") (pin "6") (pinfunction "OUT_6") (pintype "output"))
    )
    (net (code "45") (name "/ISENS_ON") (class "Default")
      (node (ref "C45") (pin "1") (pinfunction "1_1") (pintype "passive"))
      (node (ref "IC2") (pin "55") (pinfunction "CN72/RPI45/RF6_55") (pintype "bidirectional"))
      (node (ref "IC9") (pin "3") (pinfunction "VCC_3") (pintype "input"))
      (node (ref "R44") (pin "2") (pinfunction "2_2") (pintype "passive"))
    )
    (net (code "46") (name "/LCD_BL") (class "Default")
      (node (ref "IC2") (pin "28") (pinfunction "RA9/VR-/CN41_28") (pintype "bidirectional"))
      (node (ref "J2") (pin "3") (pinfunction "3_3") (pintype "passive"))
    )
    (net (code "47") (name "/LCD_CS") (class "Default")
      (node (ref "IC2") (pin "40") (pinfunction "CN75/RPI32/RF12_40") (pintype "bidirectional"))
      (node (ref "J2") (pin "10") (pinfunction "10_10") (pintype "passive"))
    )
    (net (code "48") (name "/LCD_CTL") (class "Default")
      (node (ref "IC2") (pin "50") (pinfunction "CN18/RP17/RF5_50") (pintype "bidirectional"))
      (node (ref "J2") (pin "6") (pinfunction "6_6") (pintype "passive"))
    )
    (net (code "49") (name "/LCD_RES") (class "Default")
      (node (ref "IC2") (pin "39") (pinfunction "CN76/RP31/RF13_39") (pintype "bidirectional"))
      (node (ref "J2") (pin "8") (pinfunction "8_8") (pintype "passive"))
    )
    (net (code "50") (name "/LCD_SCL") (class "Default")
      (node (ref "IC2") (pin "49") (pinfunction "CN17/RP10/RF4_49") (pintype "bidirectional"))
      (node (ref "J2") (pin "4") (pinfunction "4_4") (pintype "passive"))
    )
    (net (code "51") (name "/LCD_SI") (class "Default")
      (node (ref "IC2") (pin "32") (pinfunction "RB8/AN8/CN26/RP8_32") (pintype "bidirectional"))
      (node (ref "J2") (pin "2") (pinfunction "2_2") (pintype "passive"))
    )
    (net (code "52") (name "/LD_SM") (class "Default")
      (node (ref "IC17") (pin "25") (pinfunction "/LD_25") (pintype "bidirectional"))
      (node (ref "IC2") (pin "9") (pinfunction "RC4/CN48/RPI41_9") (pintype "bidirectional"))
    )
    (net (code "53") (name "/LOAD_ON") (class "Default")
      (node (ref "IC2") (pin "91") (pinfunction "RA6/CN39_91") (pintype "bidirectional"))
      (node (ref "Q1") (pin "2") (pinfunction "G_2") (pintype "passive"))
      (node (ref "R25") (pin "6") (pinfunction "2_6") (pintype "passive"))
    )
    (net (code "54") (name "/NC(MH_DATA)") (class "Default")
      (node (ref "IC2") (pin "59") (pinfunction "RA3/SDA2_59") (pintype "bidirectional"))
    )
    (net (code "55") (name "/OPAMP_VC") (class "Default")
      (node (ref "C19") (pin "1") (pinfunction "1_1") (pintype "passive"))
      (node (ref "C20") (pin "1") (pinfunction "1_1") (pintype "passive"))
      (node (ref "IC12") (pin "8") (pinfunction "V+_8") (pintype "input"))
      (node (ref "IC2") (pin "47") (pinfunction "CN20/RPI43/RD14_47") (pintype "bidirectional"))
      (node (ref "IC4") (pin "8") (pinfunction "V+_8") (pintype "input"))
    )
    (net (code "56") (name "/PGC") (class "Default")
      (node (ref "IC2") (pin "26") (pinfunction "RB6/AN6/PGC2/RP6_26") (pintype "bidirectional"))
      (node (ref "J4") (pin "5") (pinfunction "5_5") (pintype "passive"))
    )
    (net (code "57") (name "/PGD") (class "Default")
      (node (ref "IC2") (pin "27") (pinfunction "RB7/AN7/PGD2/RP7_27") (pintype "bidirectional"))
      (node (ref "J4") (pin "4") (pinfunction "4_4") (pintype "passive"))
    )
    (net (code "58") (name "/PHOTOCELL") (class "Default")
      (node (ref "J2") (pin "5") (pinfunction "5_5") (pintype "passive"))
      (node (ref "R11") (pin "2") (pinfunction "2_2") (pintype "passive"))
      (node (ref "R14") (pin "1") (pinfunction "1_1") (pintype "passive"))
      (node (ref "R14") (pin "2") (pinfunction "1_2") (pintype "passive"))
    )
    (net (code "59") (name "/PHOTO_PIN") (class "Default")
      (node (ref "IC2") (pin "24") (pinfunction "RB1/AN1/CN3/PGC1/RP1_24") (pintype "bidirectional"))
      (node (ref "R11") (pin "1") (pinfunction "1_1") (pintype "passive"))
    )
    (net (code "60") (name "/PHOTO_PWR") (class "Default")
      (node (ref "IC2") (pin "25") (pinfunction "RB0/AN0/CN2/PGD1/RP0_25") (pintype "bidirectional"))
      (node (ref "R14") (pin "7") (pinfunction "2_7") (pintype "passive"))
      (node (ref "R14") (pin "8") (pinfunction "2_8") (pintype "passive"))
    )
    (net (code "61") (name "/PIC_INT") (class "Default")
      (node (ref "IC2") (pin "38") (pinfunction "RA1/TCK_38") (pintype "bidirectional"))
      (node (ref "J2") (pin "7") (pinfunction "7_7") (pintype "passive"))
      (node (ref "J8") (pin "3") (pinfunction "3_3") (pintype "passive"))
    )
    (net (code "62") (name "/RTC_CS") (class "Default")
      (node (ref "IC2") (pin "79") (pinfunction "CN57/RPI42/RD12_79") (pintype "bidirectional"))
      (node (ref "IC5") (pin "6") (pinfunction "CE_6") (pintype "input"))
      (node (ref "R72") (pin "1") (pinfunction "1_1") (pintype "passive"))
    )
    (net (code "63") (name "/RTC_INT") (class "Default")
      (node (ref "IC2") (pin "80") (pinfunction "CN19/RD13_80") (pintype "bidirectional"))
      (node (ref "IC5") (pin "5") (pinfunction "/INT_5") (pintype "output"))
    )
    (net (code "64") (name "/SCL1") (class "Default")
      (node (ref "IC10") (pin "6") (pinfunction "SCL_6") (pintype "input"))
      (node (ref "IC13") (pin "6") (pinfunction "SCL_6") (pintype "input"))
      (node (ref "IC2") (pin "57") (pinfunction "RG2/SCL1/CN83_57") (pintype "bidirectional"))
      (node (ref "IC6") (pin "2") (pinfunction "SCL_2") (pintype "input"))
      (node (ref "J7") (pin "16") (pinfunction "16_16") (pintype "passive"))
      (node (ref "R74") (pin "2") (pinfunction "2_2") (pintype "passive"))
    )
    (net (code "65") (name "/SCLK1") (class "Default")
      (node (ref "IC2") (pin "77") (pinfunction "CN51/RP23/RD2_77") (pintype "bidirectional"))
      (node (ref "IC3") (pin "6") (pinfunction "C_6") (pintype "input"))
      (node (ref "IC5") (pin "10") (pinfunction "SCL_10") (pintype "input"))
    )
    (net (code "66") (name "/SCLK2") (class "Default")
      (node (ref "IC17") (pin "31") (pinfunction "ASYNC_31") (pintype "bidirectional"))
      (node (ref "IC2") (pin "10") (pinfunction "RG6/CN8/RP21_10") (pintype "bidirectional"))
      (node (ref "J2") (pin "15") (pinfunction "15_15") (pintype "passive"))
      (node (ref "J7") (pin "12") (pinfunction "12_12") (pintype "passive"))
      (node (ref "J8") (pin "5") (pinfunction "5_5") (pintype "passive"))
    )
    (net (code "67") (name "/SCLK_SM") (class "Default")
      (node (ref "IC17") (pin "26") (pinfunction "SCLK_26") (pintype "bidirectional"))
      (node (ref "IC2") (pin "8") (pinfunction "RC3/CN47/RPI40_8") (pintype "bidirectional"))
    )
    (net (code "68") (name "/SDA1") (class "Default")
      (node (ref "IC10") (pin "5") (pinfunction "SDA_5") (pintype "bidirectional"))
      (node (ref "IC13") (pin "5") (pinfunction "SDA_5") (pintype "bidirectional"))
      (node (ref "IC2") (pin "56") (pinfunction "RG3/SDA1/CN84_56") (pintype "bidirectional"))
      (node (ref "IC6") (pin "1") (pinfunction "SDA_1") (pintype "bidirectional"))
      (node (ref "J7") (pin "15") (pinfunction "15_15") (pintype "passive"))
      (node (ref "R75") (pin "2") (pinfunction "2_2") (pintype "passive"))
    )
    (net (code "69") (name "/SDI1") (class "Default")
      (node (ref "IC2") (pin "72") (pinfunction "CN49/RP11/RD0_72") (pintype "bidirectional"))
      (node (ref "IC3") (pin "2") (pinfunction "Q_2") (pintype "bidirectional"))
      (node (ref "IC5") (pin "8") (pinfunction "SDO_8") (pintype "output"))
    )
    (net (code "70") (name "/SDI2") (class "Default")
      (node (ref "IC2") (pin "11") (pinfunction "RG7/CN9/RP26_11") (pintype "bidirectional"))
      (node (ref "J2") (pin "21") (pinfunction "21_21") (pintype "passive"))
      (node (ref "J7") (pin "11") (pinfunction "11_11") (pintype "passive"))
      (node (ref "J8") (pin "8") (pinfunction "8_8") (pintype "passive"))
    )
    (net (code "71") (name "/SDO1") (class "Default")
      (node (ref "IC2") (pin "76") (pinfunction "CN50/RP24/RD1_76") (pintype "bidirectional"))
      (node (ref "IC3") (pin "5") (pinfunction "D_5") (pintype "input"))
      (node (ref "IC5") (pin "9") (pinfunction "SDI_9") (pintype "input"))
    )
    (net (code "72") (name "/SDO2") (class "Default")
      (node (ref "IC2") (pin "12") (pinfunction "CN10/RP19/RG8_12") (pintype "bidirectional"))
      (node (ref "J2") (pin "17") (pinfunction "17_17") (pintype "passive"))
      (node (ref "J7") (pin "14") (pinfunction "14_14") (pintype "passive"))
      (node (ref "J8") (pin "6") (pinfunction "6_6") (pintype "passive"))
    )
    (net (code "73") (name "/SENSE3,3V(XB_SLEEP)") (class "Default")
      (node (ref "C77") (pin "1") (pinfunction "1_1") (pintype "passive"))
      (node (ref "IC2") (pin "22") (pinfunction "RB3/AN3/CN5_22") (pintype "bidirectional"))
      (node (ref "R92") (pin "2") (pinfunction "2_2") (pintype "passive"))
    )
    (net (code "74") (name "/SERIAL_ON(VPC_B)") (class "Default")
      (node (ref "IC2") (pin "74") (pinfunction "RC14/SOSCO/CN0/RPI37_74") (pintype "bidirectional"))
      (node (ref "Q5") (pin "5") (pinfunction "Q1G_5") (pintype "input"))
      (node (ref "R82") (pin "1") (pinfunction "1_1") (pintype "passive"))
    )
    (net (code "75") (name "/SM_C4A") (class "Default")
      (node (ref "IC17") (pin "4") (pinfunction "C4A_4") (pintype "bidirectional"))
      (node (ref "J2") (pin "18") (pinfunction "18_18") (pintype "passive"))
    )
    (net (code "76") (name "/SM_C8A") (class "Default")
      (node (ref "IC17") (pin "3") (pinfunction "C8A_3") (pintype "bidirectional"))
      (node (ref "J2") (pin "22") (pinfunction "22_22") (pintype "passive"))
    )
    (net (code "77") (name "/SM_CLK_A") (class "Default")
      (node (ref "IC17") (pin "7") (pinfunction "CLKA_7") (pintype "bidirectional"))
      (node (ref "J2") (pin "16") (pinfunction "16_16") (pintype "passive"))
    )
    (net (code "78") (name "/SM_DATA") (class "Default")
      (node (ref "IC17") (pin "29") (pinfunction "DATA_29") (pintype "bidirectional"))
      (node (ref "IC2") (pin "14") (pinfunction "CN11/RP27/RG9_14") (pintype "bidirectional"))
    )
    (net (code "79") (name "/SM_DET_A") (class "Default")
      (node (ref "IC17") (pin "2") (pinfunction "PRESA_2") (pintype "bidirectional"))
      (node (ref "J2") (pin "24") (pinfunction "24_24") (pintype "passive"))
    )
    (net (code "80") (name "/SM_IO_A") (class "Default")
      (node (ref "IC17") (pin "5") (pinfunction "IOA_5") (pintype "bidirectional"))
      (node (ref "J2") (pin "20") (pinfunction "20_20") (pintype "passive"))
    )
    (net (code "81") (name "/SM_RST") (class "Default")
      (node (ref "IC17") (pin "30") (pinfunction "RIN_30") (pintype "bidirectional"))
      (node (ref "IC2") (pin "5") (pinfunction "CN65/SDA3/RE7_5") (pintype "bidirectional"))
    )
    (net (code "82") (name "/SM_RST_A") (class "Default")
      (node (ref "IC17") (pin "6") (pinfunction "RSTA_6") (pintype "bidirectional"))
      (node (ref "J2") (pin "14") (pinfunction "14_14") (pintype "passive"))
    )
    (net (code "83") (name "/SM_SYNC") (class "Default")
      (node (ref "IC17") (pin "32") (pinfunction "SYNC_32") (pintype "bidirectional"))
      (node (ref "IC2") (pin "4") (pinfunction "CN64/SCL3/RE6_4") (pintype "bidirectional"))
    )
    (net (code "84") (name "/SM_VCC_A") (class "Default")
      (node (ref "IC17") (pin "8") (pinfunction "VCCA_8") (pintype "bidirectional"))
      (node (ref "J2") (pin "12") (pinfunction "12_12") (pintype "passive"))
    )
    (net (code "85") (name "/SNDR") (class "Default")
      (node (ref "IC2") (pin "35") (pinfunction "RB11/AN11/CN29_35") (pintype "bidirectional"))
      (node (ref "J2") (pin "1") (pinfunction "1_1") (pintype "passive"))
    )
    (net (code "86") (name "/U2CTL(CM_RTS)") (class "Default")
      (node (ref "IC2") (pin "19") (pinfunction "RPI34/CN67/RE9_19") (pintype "bidirectional"))
      (node (ref "J2") (pin "26") (pinfunction "26_26") (pintype "passive"))
      (node (ref "J7") (pin "6") (pinfunction "6_6") (pintype "passive"))
    )
    (net (code "87") (name "/U2RX") (class "Default")
      (node (ref "IC2") (pin "81") (pinfunction "CN13/RP25/RD4_81") (pintype "bidirectional"))
      (node (ref "J7") (pin "4") (pinfunction "4_4") (pintype "passive"))
    )
    (net (code "88") (name "/U2TX") (class "Default")
      (node (ref "IC2") (pin "82") (pinfunction "CN14/RP20/RD5_82") (pintype "bidirectional"))
      (node (ref "J7") (pin "2") (pinfunction "2_2") (pintype "passive"))
    )
    (net (code "89") (name "/VBATLAN-TO-MB({slash}RAM_CS)") (class "Default")
      (node (ref "IC2") (pin "3") (pinfunction "CN63/RE5_3") (pintype "bidirectional"))
      (node (ref "J7") (pin "13") (pinfunction "13_13") (pintype "passive"))
    )
    (net (code "90") (name "/VBATMB-TO-LAN(CM_RST)") (class "Default")
      (node (ref "IC2") (pin "98") (pinfunction "CN60/RE2_98") (pintype "bidirectional"))
      (node (ref "J7") (pin "5") (pinfunction "5_5") (pintype "passive"))
    )
    (net (code "91") (name "/VBATSENSE(SM_FAULT)") (class "Default")
      (node (ref "C78") (pin "1") (pinfunction "1_1") (pintype "passive"))
      (node (ref "IC2") (pin "21") (pinfunction "RB4/AN4/CN6/RP28_21") (pintype "bidirectional"))
      (node (ref "R93") (pin "2") (pinfunction "2_2") (pintype "passive"))
    )
    (net (code "92") (name "/VBAT_H(U3TX)") (class "Default")
      (node (ref "IC15") (pin "7") (pinfunction "OUT_7") (pintype "output"))
      (node (ref "IC2") (pin "33") (pinfunction "RB9/AN9/CN27/RP9_33") (pintype "bidirectional"))
    )
    (net (code "93") (name "/VBAT_L(U3RX)") (class "Default")
      (node (ref "IC15") (pin "1") (pinfunction "OUT_1") (pintype "output"))
      (node (ref "IC2") (pin "23") (pinfunction "RB2/AN2/CN4/RP13_23") (pintype "bidirectional"))
    )
    (net (code "94") (name "/VPC_A") (class "Default")
      (node (ref "IC2") (pin "69") (pinfunction "CN54/RP4/RD9_69") (pintype "bidirectional"))
      (node (ref "R2") (pin "7") (pinfunction "2_7") (pintype "passive"))
    )
    (net (code "95") (name "/VPC_B(XB_RTS)") (class "Default")
      (node (ref "IC2") (pin "48") (pinfunction "CN21/RP5/RD15_48") (pintype "bidirectional"))
      (node (ref "R2") (pin "5") (pinfunction "2_5") (pintype "passive"))
    )
    (net (code "96") (name "/VPS-ON(CM_ON)") (class "Default")
      (node (ref "IC2") (pin "100") (pinfunction "CN62/RE4_100") (pintype "bidirectional"))
      (node (ref "J7") (pin "8") (pinfunction "8_8") (pintype "passive"))
    )
    (net (code "97") (name "/VPS-SENSE(CM_RING)") (class "Default")
      (node (ref "IC2") (pin "99") (pinfunction "CN61/RE3_99") (pintype "bidirectional"))
      (node (ref "J7") (pin "3") (pinfunction "3_3") (pintype "passive"))
    )
    (net (code "98") (name "/VREF1.25V") (class "Default")
      (node (ref "C67") (pin "1") (pinfunction "1_1") (pintype "passive"))
      (node (ref "IC15") (pin "2") (pinfunction "-IN_2") (pintype "input"))
      (node (ref "IC15") (pin "6") (pinfunction "-IN_6") (pintype "input"))
      (node (ref "R68") (pin "2") (pinfunction "2_2") (pintype "passive"))
      (node (ref "R69") (pin "1") (pinfunction "1_1") (pintype "passive"))
    )
    (net (code "99") (name "/VREF2.5") (class "Default")
      (node (ref "C3") (pin "1") (pinfunction "1_1") (pintype "passive"))
      (node (ref "IC1") (pin "2") (pinfunction "VOUT_2") (pintype "output"))
      (node (ref "IC2") (pin "29") (pinfunction "RA10/VR+/CN42_29") (pintype "bidirectional"))
      (node (ref "R68") (pin "1") (pinfunction "1_1") (pintype "passive"))
      (node (ref "TP7") (pin "P$1") (pinfunction "TP_P$1") (pintype "passive"))
    )
    (net (code "100") (name "/VSENSEA") (class "Default")
      (node (ref "IC2") (pin "43") (pinfunction "RB14/AN14/CN32/RP14_43") (pintype "bidirectional"))
      (node (ref "IC4") (pin "1") (pinfunction "OUT_1") (pintype "output"))
      (node (ref "IC4") (pin "2") (pinfunction "-IN_2") (pintype "input"))
    )
    (net (code "101") (name "/VSENSEB") (class "Default")
      (node (ref "IC2") (pin "42") (pinfunction "RB13/AN13/CN31_42") (pintype "bidirectional"))
      (node (ref "IC4") (pin "6") (pinfunction "-IN_6") (pintype "input"))
      (node (ref "IC4") (pin "7") (pinfunction "OUT_7") (pintype "output"))
    )
    (net (code "102") (name "/VSOLAR") (class "Default")
      (node (ref "D9") (pin "A") (pinfunction "A_A") (pintype "passive"))
      (node (ref "J16") (pin "2") (pinfunction "2_2") (pintype "passive"))
      (node (ref "J8") (pin "2") (pinfunction "2_2") (pintype "passive"))
      (node (ref "R41") (pin "1") (pinfunction "1_1") (pintype "passive"))
      (node (ref "R95") (pin "1") (pinfunction "1_1") (pintype "passive"))
      (node (ref "TP12") (pin "P$1") (pinfunction "TP_P$1") (pintype "passive"))
    )
    (net (code "103") (name "/VS_SENSE") (class "Default")
      (node (ref "IC12") (pin "1") (pinfunction "OUT_1") (pintype "output"))
      (node (ref "IC12") (pin "2") (pinfunction "-IN_2") (pintype "input"))
      (node (ref "IC2") (pin "41") (pinfunction "RB12/AN12/CN30_41") (pintype "bidirectional"))
    )
    (net (code "104") (name "/{slash}3.3V1_ON") (class "Default")
      (node (ref "IC2") (pin "95") (pinfunction "CN81/RG14_95") (pintype "bidirectional"))
      (node (ref "Q17") (pin "2") (pinfunction "G_2") (pintype "passive"))
    )
    (net (code "105") (name "/{slash}CELL_3VON") (class "Default")
      (node (ref "IC2") (pin "94") (pinfunction "CN59/RE1_94") (pintype "bidirectional"))
      (node (ref "Q17") (pin "5") (pinfunction "G_5") (pintype "passive"))
    )
    (net (code "106") (name "/{slash}CHRG_SD") (class "Default")
      (node (ref "IC2") (pin "96") (pinfunction "CN79/RG12_96") (pintype "bidirectional"))
      (node (ref "R13") (pin "1") (pinfunction "1_1") (pintype "passive"))
    )
    (net (code "107") (name "/{slash}CL_CS1") (class "Default")
      (node (ref "IC2") (pin "1") (pinfunction "CN82/RG15_1") (pintype "bidirectional"))
      (node (ref "J2") (pin "19") (pinfunction "19_19") (pintype "passive"))
    )
    (net (code "108") (name "/{slash}CL_CS2") (class "Default")
      (node (ref "IC2") (pin "17") (pinfunction "RA0/TMS_17") (pintype "bidirectional"))
      (node (ref "J8") (pin "7") (pinfunction "7_7") (pintype "passive"))
    )
    (net (code "109") (name "/{slash}FMEM1_CS") (class "Default")
      (node (ref "IC2") (pin "93") (pinfunction "CN58/RE0_93") (pintype "bidirectional"))
      (node (ref "IC3") (pin "1") (pinfunction "/S_1") (pintype "input"))
      (node (ref "R71") (pin "1") (pinfunction "1_1") (pintype "passive"))
    )
    (net (code "110") (name "/{slash}MCLR") (class "Default")
      (node (ref "IC11") (pin "4") (pinfunction "GP2/T0CK_4") (pintype "bidirectional"))
      (node (ref "IC2") (pin "13") (pinfunction "MCLR_13") (pintype "input"))
      (node (ref "J4") (pin "1") (pinfunction "1_1") (pintype "passive"))
      (node (ref "R73") (pin "1") (pinfunction "1_1") (pintype "passive"))
    )
    (net (code "111") (name "/{slash}MCLR2") (class "Default")
      (node (ref "IC11") (pin "6") (pinfunction "GP3/MCLR_6") (pintype "bidirectional"))
      (node (ref "J10") (pin "1") (pinfunction "1_1") (pintype "passive"))
    )
    (net (code "112") (name "/{slash}SM_FAULT(MH_STROBE)") (class "Default")
      (node (ref "IC17") (pin "24") (pinfunction "-FAULT_24") (pintype "bidirectional"))
      (node (ref "IC2") (pin "58") (pinfunction "RA2/SCL2_58") (pintype "bidirectional"))
    )
    (net (code "113") (name "BATA") (class "Default")
      (node (ref "C26") (pin "1") (pinfunction "1_1") (pintype "passive"))
      (node (ref "D2") (pin "C") (pinfunction "C_C") (pintype "passive"))
      (node (ref "F1") (pin "1") (pinfunction "1_1") (pintype "passive"))
      (node (ref "F1") (pin "2") (pinfunction "2_2") (pintype "passive"))
      (node (ref "J9") (pin "2") (pinfunction "2_2") (pintype "passive"))
      (node (ref "Q6") (pin "1") (pinfunction "S_1") (pintype "passive"))
      (node (ref "Q8") (pin "1") (pinfunction "S_1") (pintype "passive"))
      (node (ref "Q9") (pin "1") (pinfunction "S_1") (pintype "passive"))
      (node (ref "R15") (pin "2") (pinfunction "2_2") (pintype "passive"))
      (node (ref "R16") (pin "1") (pinfunction "1_1") (pintype "passive"))
      (node (ref "R19") (pin "2") (pinfunction "2_2") (pintype "passive"))
      (node (ref "R4") (pin "1") (pinfunction "1_1") (pintype "passive"))
      (node (ref "R52") (pin "2") (pinfunction "2_2") (pintype "passive"))
      (node (ref "TP3") (pin "P$1") (pinfunction "TP_P$1") (pintype "passive"))
    )
    (net (code "114") (name "BATB") (class "Default")
      (node (ref "C34") (pin "1") (pinfunction "1_1") (pintype "passive"))
      (node (ref "D12") (pin "1+") (pinfunction "C_1+") (pintype "passive"))
      (node (ref "D4") (pin "C") (pinfunction "C_C") (pintype "passive"))
      (node (ref "F2") (pin "1") (pinfunction "1_1") (pintype "passive"))
      (node (ref "F2") (pin "2") (pinfunction "2_2") (pintype "passive"))
      (node (ref "J11") (pin "2") (pinfunction "2_2") (pintype "passive"))
      (node (ref "L3") (pin "2") (pinfunction "2_2") (pintype "passive"))
      (node (ref "Q14") (pin "1") (pinfunction "S_1") (pintype "passive"))
      (node (ref "Q15") (pin "1") (pinfunction "S_1") (pintype "passive"))
      (node (ref "R10") (pin "1") (pinfunction "1_1") (pintype "passive"))
      (node (ref "R16") (pin "3") (pinfunction "1_3") (pintype "passive"))
      (node (ref "R29") (pin "2") (pinfunction "2_2") (pintype "passive"))
      (node (ref "R30") (pin "2") (pinfunction "2_2") (pintype "passive"))
      (node (ref "TP4") (pin "P$1") (pinfunction "TP_P$1") (pintype "passive"))
    )
    (net (code "115") (name "DGND") (class "Default")
      (node (ref "C1") (pin "2") (pinfunction "2_2") (pintype "passive"))
      (node (ref "C10") (pin "1") (pinfunction "1_1") (pintype "passive"))
      (node (ref "C11") (pin "2") (pinfunction "2_2") (pintype "passive"))
      (node (ref "C13") (pin "2") (pinfunction "2_2") (pintype "passive"))
      (node (ref "C15") (pin "1") (pinfunction "1_1") (pintype "passive"))
      (node (ref "C16") (pin "2") (pinfunction "2_2") (pintype "passive"))
      (node (ref "C17") (pin "1") (pinfunction "1_1") (pintype "passive"))
      (node (ref "C18") (pin "2") (pinfunction "2_2") (pintype "passive"))
      (node (ref "C19") (pin "2") (pinfunction "2_2") (pintype "passive"))
      (node (ref "C2") (pin "2") (pinfunction "2_2") (pintype "passive"))
      (node (ref "C20") (pin "2") (pinfunction "2_2") (pintype "passive"))
      (node (ref "C21") (pin "1") (pinfunction "1_1") (pintype "passive"))
      (node (ref "C22") (pin "1") (pinfunction "1_1") (pintype "passive"))
      (node (ref "C23") (pin "2") (pinfunction "2_2") (pintype "passive"))
      (node (ref "C24") (pin "2") (pinfunction "2_2") (pintype "passive"))
      (node (ref "C25") (pin "2") (pinfunction "2_2") (pintype "passive"))
      (node (ref "C26") (pin "2") (pinfunction "2_2") (pintype "passive"))
      (node (ref "C28") (pin "2") (pinfunction "2_2") (pintype "passive"))
      (node (ref "C29") (pin "2") (pinfunction "2_2") (pintype "passive"))
      (node (ref "C3") (pin "2") (pinfunction "2_2") (pintype "passive"))
      (node (ref "C30") (pin "2") (pinfunction "2_2") (pintype "passive"))
      (node (ref "C32") (pin "2") (pinfunction "2_2") (pintype "passive"))
      (node (ref "C34") (pin "2") (pinfunction "2_2") (pintype "passive"))
      (node (ref "C35") (pin "2") (pinfunction "2_2") (pintype "passive"))
      (node (ref "C36") (pin "2") (pinfunction "2_2") (pintype "passive"))
      (node (ref "C4") (pin "2") (pinfunction "2_2") (pintype "passive"))
      (node (ref "C41") (pin "2") (pinfunction "2_2") (pintype "passive"))
      (node (ref "C42") (pin "2") (pinfunction "2_2") (pintype "passive"))
      (node (ref "C45") (pin "2") (pinfunction "2_2") (pintype "passive"))
      (node (ref "C46") (pin "2") (pinfunction "2_2") (pintype "passive"))
      (node (ref "C47") (pin "2") (pinfunction "2_2") (pintype "passive"))
      (node (ref "C48") (pin "1") (pinfunction "1_1") (pintype "passive"))
      (node (ref "C49") (pin "2") (pinfunction "2_2") (pintype "passive"))
      (node (ref "C5") (pin "2") (pinfunction "2_2") (pintype "passive"))
      (node (ref "C51") (pin "2") (pinfunction "2_2") (pintype "passive"))
      (node (ref "C56") (pin "2") (pinfunction "2_2") (pintype "passive"))
      (node (ref "C57") (pin "2") (pinfunction "2_2") (pintype "passive"))
      (node (ref "C58") (pin "2") (pinfunction "2_2") (pintype "passive"))
      (node (ref "C59") (pin "2") (pinfunction "2_2") (pintype "passive"))
      (node (ref "C6") (pin "2") (pinfunction "2_2") (pintype "passive"))
      (node (ref "C60") (pin "1") (pinfunction "1_1") (pintype "passive"))
      (node (ref "C61") (pin "-") (pinfunction "-_-") (pintype "passive"))
      (node (ref "C64") (pin "2") (pinfunction "2_2") (pintype "passive"))
      (node (ref "C65") (pin "2") (pinfunction "2_2") (pintype "passive"))
      (node (ref "C66") (pin "2") (pinfunction "2_2") (pintype "passive"))
      (node (ref "C67") (pin "2") (pinfunction "2_2") (pintype "passive"))
      (node (ref "C68") (pin "2") (pinfunction "2_2") (pintype "passive"))
      (node (ref "C69") (pin "-") (pinfunction "-_-") (pintype "passive"))
      (node (ref "C7") (pin "2") (pinfunction "2_2") (pintype "passive"))
      (node (ref "C70") (pin "-") (pinfunction "-_-") (pintype "passive"))
      (node (ref "C71") (pin "2") (pinfunction "2_2") (pintype "passive"))
      (node (ref "C73") (pin "2") (pinfunction "2_2") (pintype "passive"))
      (node (ref "C74") (pin "2") (pinfunction "2_2") (pintype "passive"))
      (node (ref "C75") (pin "2") (pinfunction "2_2") (pintype "passive"))
      (node (ref "C76") (pin "2") (pinfunction "2_2") (pintype "passive"))
      (node (ref "C77") (pin "2") (pinfunction "2_2") (pintype "passive"))
      (node (ref "C78") (pin "2") (pinfunction "2_2") (pintype "passive"))
      (node (ref "C8") (pin "2") (pinfunction "2_2") (pintype "passive"))
      (node (ref "C9") (pin "2") (pinfunction "2_2") (pintype "passive"))
      (node (ref "D11") (pin "-") (pinfunction "A_-") (pintype "passive"))
      (node (ref "D3") (pin "A") (pinfunction "A_A") (pintype "passive"))
      (node (ref "D8") (pin "1") (pinfunction "A_1") (pintype "passive"))
      (node (ref "D8") (pin "2") (pinfunction "A_2") (pintype "passive"))
      (node (ref "IC1") (pin "3") (pinfunction "GND_3") (pintype "input"))
      (node (ref "IC10") (pin "1") (pinfunction "A0_1") (pintype "input"))
      (node (ref "IC10") (pin "2") (pinfunction "A1_2") (pintype "input"))
      (node (ref "IC10") (pin "3") (pinfunction "A2_3") (pintype "input"))
      (node (ref "IC10") (pin "4") (pinfunction "GND_4") (pintype "input"))
      (node (ref "IC10") (pin "7") (pinfunction "WP_7") (pintype "input"))
      (node (ref "IC11") (pin "2") (pinfunction "VSS_2") (pintype "input"))
      (node (ref "IC12") (pin "4") (pinfunction "V-_4") (pintype "input"))
      (node (ref "IC13") (pin "1") (pinfunction "A0_1") (pintype "input"))
      (node (ref "IC13") (pin "3") (pinfunction "A2_3") (pintype "input"))
      (node (ref "IC13") (pin "4") (pinfunction "GND_4") (pintype "input"))
      (node (ref "IC14") (pin "2") (pinfunction "GND_2") (pintype "input"))
      (node (ref "IC15") (pin "4") (pinfunction "V-_4") (pintype "input"))
      (node (ref "IC16") (pin "4") (pinfunction "V-_4") (pintype "input"))
      (node (ref "IC17") (pin "10") (pinfunction "PGND_10") (pintype "input"))
      (node (ref "IC17") (pin "21") (pinfunction "PRESB_21") (pintype "bidirectional"))
      (node (ref "IC17") (pin "9") (pinfunction "SGND_9") (pintype "input"))
      (node (ref "IC17") (pin "PAD") (pinfunction "PAD_PAD") (pintype "input"))
      (node (ref "IC2") (pin "15") (pinfunction "VSS15_15") (pintype "input"))
      (node (ref "IC2") (pin "31") (pinfunction "AVSS_31") (pintype "input"))
      (node (ref "IC2") (pin "36") (pinfunction "VSS36_36") (pintype "input"))
      (node (ref "IC2") (pin "45") (pinfunction "VSS45_45") (pintype "input"))
      (node (ref "IC2") (pin "65") (pinfunction "VSS65_65") (pintype "input"))
      (node (ref "IC2") (pin "75") (pinfunction "VSS75_75") (pintype "input"))
      (node (ref "IC3") (pin "4") (pinfunction "GND_4") (pintype "input"))
      (node (ref "IC4") (pin "4") (pinfunction "V-_4") (pintype "input"))
      (node (ref "IC5") (pin "12") (pinfunction "CLKOE_12") (pintype "input"))
      (node (ref "IC5") (pin "7") (pinfunction "VSS_7") (pintype "input"))
      (node (ref "IC6") (pin "4") (pinfunction "GND_4") (pintype "input"))
      (node (ref "IC6") (pin "5") (pinfunction "A2_5") (pintype "input"))
      (node (ref "IC6") (pin "6") (pinfunction "A1_6") (pintype "input"))
      (node (ref "IC7") (pin "4") (pinfunction "GND_4") (pintype "input"))
      (node (ref "IC9") (pin "2") (pinfunction "GND_2") (pintype "input"))
      (node (ref "IC9") (pin "4") (pinfunction "VIN+_4") (pintype "input"))
      (node (ref "J1") (pin "1") (pinfunction "1_1") (pintype "passive"))
      (node (ref "J10") (pin "3") (pinfunction "3_3") (pintype "passive"))
      (node (ref "J16") (pin "1") (pinfunction "1_1") (pintype "passive"))
      (node (ref "J17") (pin "C5") (pinfunction "C5_C5") (pintype "bidirectional"))
      (node (ref "J2") (pin "23") (pinfunction "23_23") (pintype "passive"))
      (node (ref "J4") (pin "3") (pinfunction "3_3") (pintype "passive"))
      (node (ref "J5") (pin "1") (pinfunction "1_1") (pintype "passive"))
      (node (ref "J6") (pin "1") (pinfunction "1_1") (pintype "passive"))
      (node (ref "J7") (pin "9") (pinfunction "9_9") (pintype "passive"))
      (node (ref "J8") (pin "1") (pinfunction "1_1") (pintype "passive"))
      (node (ref "L2") (pin "2") (pinfunction "2_2") (pintype "passive"))
      (node (ref "L4") (pin "2") (pinfunction "1_2") (pintype "passive"))
      (node (ref "PCB1") (pin "1") (pinfunction "GND1_1") (pintype "bidirectional"))
      (node (ref "PCB1") (pin "2") (pinfunction "GND2_2") (pintype "bidirectional"))
      (node (ref "PCB1") (pin "3") (pinfunction "GND3_3") (pintype "bidirectional"))
      (node (ref "PCB1") (pin "4") (pinfunction "GND4_4") (pintype "bidirectional"))
      (node (ref "PCB1") (pin "5") (pinfunction "GND5_5") (pintype "bidirectional"))
      (node (ref "PCB1") (pin "6") (pinfunction "GND6_6") (pintype "bidirectional"))
      (node (ref "Q1") (pin "1") (pinfunction "S_1") (pintype "passive"))
      (node (ref "Q10") (pin "1") (pinfunction "S_1") (pintype "passive"))
      (node (ref "Q10") (pin "4") (pinfunction "S_4") (pintype "passive"))
      (node (ref "Q12") (pin "1") (pinfunction "S_1") (pintype "passive"))
      (node (ref "Q12") (pin "4") (pinfunction "S_4") (pintype "passive"))
      (node (ref "Q13") (pin "1") (pinfunction "S_1") (pintype "passive"))
      (node (ref "Q13") (pin "4") (pinfunction "S_4") (pintype "passive"))
      (node (ref "Q16") (pin "1") (pinfunction "S_1") (pintype "passive"))
      (node (ref "Q16") (pin "4") (pinfunction "S_4") (pintype "passive"))
      (node (ref "Q18") (pin "1") (pinfunction "S_1") (pintype "passive"))
      (node (ref "Q18") (pin "4") (pinfunction "S_4") (pintype "passive"))
      (node (ref "Q4") (pin "1") (pinfunction "S_1") (pintype "passive"))
      (node (ref "Q4") (pin "4") (pinfunction "S_4") (pintype "passive"))
      (node (ref "R1") (pin "3") (pinfunction "1_3") (pintype "passive"))
      (node (ref "R1") (pin "5") (pinfunction "2_5") (pintype "passive"))
      (node (ref "R1") (pin "7") (pinfunction "2_7") (pintype "passive"))
      (node (ref "R1") (pin "8") (pinfunction "2_8") (pintype "passive"))
      (node (ref "R12") (pin "2") (pinfunction "2_2") (pintype "passive"))
      (node (ref "R22") (pin "1") (pinfunction "1_1") (pintype "passive"))
      (node (ref "R23") (pin "1") (pinfunction "1_1") (pintype "passive"))
      (node (ref "R24") (pin "1") (pinfunction "1_1") (pintype "passive"))
      (node (ref "R25") (pin "4") (pinfunction "1_4") (pintype "passive"))
      (node (ref "R28") (pin "2") (pinfunction "2_2") (pintype "passive"))
      (node (ref "R33") (pin "1") (pinfunction "1_1") (pintype "passive"))
      (node (ref "R34") (pin "2") (pinfunction "2_2") (pintype "passive"))
      (node (ref "R45") (pin "1") (pinfunction "1_1") (pintype "passive"))
      (node (ref "R5") (pin "2") (pinfunction "2_2") (pintype "passive"))
      (node (ref "R55") (pin "1") (pinfunction "1_1") (pintype "passive"))
      (node (ref "R61") (pin "2") (pinfunction "2_2") (pintype "passive"))
      (node (ref "R64") (pin "2") (pinfunction "2_2") (pintype "passive"))
      (node (ref "R69") (pin "2") (pinfunction "2_2") (pintype "passive"))
      (node (ref "R72") (pin "2") (pinfunction "2_2") (pintype "passive"))
      (node (ref "R79") (pin "1") (pinfunction "1_1") (pintype "passive"))
      (node (ref "R8") (pin "2") (pinfunction "2_2") (pintype "passive"))
      (node (ref "R81") (pin "2") (pinfunction "2_2") (pintype "passive"))
      (node (ref "R82") (pin "2") (pinfunction "2_2") (pintype "passive"))
      (node (ref "R85") (pin "2") (pinfunction "2_2") (pintype "passive"))
      (node (ref "R87") (pin "2") (pinfunction "2_2") (pintype "passive"))
      (node (ref "R90") (pin "1") (pinfunction "1_1") (pintype "passive"))
      (node (ref "R91") (pin "2") (pinfunction "2_2") (pintype "passive"))
      (node (ref "R94") (pin "2") (pinfunction "2_2") (pintype "passive"))
      (node (ref "R98") (pin "2") (pinfunction "2_2") (pintype "passive"))
      (node (ref "TP5") (pin "P$1") (pinfunction "TP_P$1") (pintype "passive"))
    )
    (net (code "116") (name "Net-(B1-Pad-)") (class "Default")
      (node (ref "B1") (pin "-") (pinfunction "-_-") (pintype "passive"))
      (node (ref "B2") (pin "-") (pinfunction "-_-") (pintype "passive"))
      (node (ref "R94") (pin "1") (pinfunction "1_1") (pintype "passive"))
    )
    (net (code "117") (name "Net-(B2-Pad+)") (class "Default")
      (node (ref "B2") (pin "+") (pinfunction "+_+") (pintype "passive"))
      (node (ref "R86") (pin "1") (pinfunction "1_1") (pintype "passive"))
    )
    (net (code "118") (name "Net-(C36-Pad1)") (class "Default")
      (node (ref "C36") (pin "1") (pinfunction "1_1") (pintype "passive"))
      (node (ref "R27") (pin "1") (pinfunction "1_1") (pintype "passive"))
    )
    (net (code "119") (name "Net-(C71-Pad1)") (class "Default")
      (node (ref "C71") (pin "1") (pinfunction "1_1") (pintype "passive"))
      (node (ref "L7") (pin "1") (pinfunction "1_1") (pintype "passive"))
      (node (ref "R83") (pin "1") (pinfunction "1_1") (pintype "passive"))
      (node (ref "R84") (pin "2") (pinfunction "2_2") (pintype "passive"))
    )
    (net (code "120") (name "Net-(D1-A1)") (class "Default")
      (node (ref "B1") (pin "+") (pinfunction "+_+") (pintype "passive"))
      (node (ref "D1") (pin "1") (pinfunction "A1_1") (pintype "passive"))
    )
    (net (code "121") (name "Net-(D1-K)") (class "Default")
      (node (ref "C25") (pin "1") (pinfunction "1_1") (pintype "passive"))
      (node (ref "D1") (pin "3") (pinfunction "K_3") (pintype "passive"))
      (node (ref "IC5") (pin "14") (pinfunction "VDD_14") (pintype "input"))
      (node (ref "R86") (pin "2") (pinfunction "2_2") (pintype "passive"))
      (node (ref "TP9") (pin "P$1") (pinfunction "TP_P$1") (pintype "passive"))
    )
    (net (code "122") (name "Net-(D3-K)") (class "Default")
      (node (ref "D3") (pin "C") (pinfunction "K_C") (pintype "passive"))
      (node (ref "L1") (pin "1") (pinfunction "1_1") (pintype "passive"))
      (node (ref "Q11") (pin "3") (pinfunction "D_3") (pintype "passive"))
    )
    (net (code "123") (name "Net-(D5-K)") (class "Default")
      (node (ref "C37") (pin "2") (pinfunction "2_2") (pintype "passive"))
      (node (ref "D5") (pin "2") (pinfunction "K_2") (pintype "passive"))
      (node (ref "IC8") (pin "17") (pinfunction "VBOOT_17") (pintype "input"))
    )
    (net (code "124") (name "Net-(D5-KA)") (class "Default")
      (node (ref "C31") (pin "1") (pinfunction "1_1") (pintype "passive"))
      (node (ref "D5") (pin "3") (pinfunction "KA_3") (pintype "passive"))
    )
    (net (code "125") (name "Net-(D7-C)") (class "Default")
      (node (ref "D7") (pin "3") (pinfunction "C_3") (pintype "passive"))
      (node (ref "R25") (pin "1") (pinfunction "1_1") (pintype "passive"))
      (node (ref "R25") (pin "2") (pinfunction "1_2") (pintype "passive"))
      (node (ref "R7") (pin "6") (pinfunction "2_6") (pintype "passive"))
    )
    (net (code "126") (name "Net-(D8A-AK)") (class "Default")
      (node (ref "C64") (pin "1") (pinfunction "1_1") (pintype "passive"))
      (node (ref "D8") (pin "6") (pinfunction "AK_6") (pintype "passive"))
      (node (ref "R2") (pin "3") (pinfunction "1_3") (pintype "passive"))
      (node (ref "R2") (pin "4") (pinfunction "1_4") (pintype "passive"))
    )
    (net (code "127") (name "Net-(D8B-AK)") (class "Default")
      (node (ref "C65") (pin "1") (pinfunction "1_1") (pintype "passive"))
      (node (ref "D8") (pin "3") (pinfunction "AK_3") (pintype "passive"))
      (node (ref "R2") (pin "1") (pinfunction "1_1") (pintype "passive"))
      (node (ref "R2") (pin "2") (pinfunction "1_2") (pintype "passive"))
    )
    (net (code "128") (name "Net-(D10-K)") (class "Default")
      (node (ref "C51") (pin "1") (pinfunction "1_1") (pintype "passive"))
      (node (ref "C74") (pin "1") (pinfunction "1_1") (pintype "passive"))
      (node (ref "D10") (pin "C") (pinfunction "K_C") (pintype "passive"))
      (node (ref "L3") (pin "1") (pinfunction "1_1") (pintype "passive"))
    )
    (net (code "129") (name "Net-(D11-C)") (class "Default")
      (node (ref "C30") (pin "1") (pinfunction "1_1") (pintype "passive"))
      (node (ref "C33") (pin "2") (pinfunction "2_2") (pintype "passive"))
      (node (ref "D11") (pin "+") (pinfunction "C_+") (pintype "passive"))
      (node (ref "L1") (pin "2") (pinfunction "2_2") (pintype "passive"))
      (node (ref "R37") (pin "1") (pinfunction "1_1") (pintype "passive"))
      (node (ref "R84") (pin "1") (pinfunction "1_1") (pintype "passive"))
    )
    (net (code "130") (name "Net-(D12-A)") (class "Default")
      (node (ref "D12") (pin "2") (pinfunction "A_2") (pintype "passive"))
      (node (ref "R51") (pin "1") (pinfunction "1_1") (pintype "passive"))
    )
    (net (code "131") (name "Net-(IC1-VIN)") (class "Default")
      (node (ref "C4") (pin "1") (pinfunction "1_1") (pintype "passive"))
      (node (ref "C59") (pin "1") (pinfunction "1_1") (pintype "passive"))
      (node (ref "IC1") (pin "1") (pinfunction "VIN_1") (pintype "input"))
      (node (ref "R57") (pin "2") (pinfunction "2_2") (pintype "passive"))
    )
    (net (code "132") (name "Net-(IC2-AVDD)") (class "Default")
      (node (ref "C58") (pin "1") (pinfunction "1_1") (pintype "passive"))
      (node (ref "C7") (pin "1") (pinfunction "1_1") (pintype "passive"))
      (node (ref "IC2") (pin "30") (pinfunction "AVDD_30") (pintype "input"))
      (node (ref "R3") (pin "1") (pinfunction "1_1") (pintype "passive"))
    )
    (net (code "133") (name "Net-(IC2-OSC1{slash}CLKI{slash}RC12)") (class "Default")
      (node (ref "C17") (pin "2") (pinfunction "2_2") (pintype "passive"))
      (node (ref "IC2") (pin "63") (pinfunction "OSC1/CLKI/RC12_63") (pintype "bidirectional"))
      (node (ref "Q20") (pin "3") (pinfunction "2_3") (pintype "passive"))
    )
    (net (code "134") (name "Net-(IC2-OSC2{slash}CLKO{slash}RC15)") (class "Default")
      (node (ref "C21") (pin "2") (pinfunction "2_2") (pintype "passive"))
      (node (ref "IC2") (pin "64") (pinfunction "OSC2/CLKO/RC15_64") (pintype "bidirectional"))
      (node (ref "Q20") (pin "1") (pinfunction "1_1") (pintype "passive"))
    )
    (net (code "135") (name "Net-(IC2-VDDCORE)") (class "Default")
      (node (ref "C10") (pin "2") (pinfunction "2_2") (pintype "passive"))
      (node (ref "C60") (pin "2") (pinfunction "2_2") (pintype "passive"))
      (node (ref "IC2") (pin "85") (pinfunction "VDDCORE_85") (pintype "input"))
    )
    (net (code "136") (name "Net-(IC4A-+IN)") (class "Default")
      (node (ref "C13") (pin "1") (pinfunction "1_1") (pintype "passive"))
      (node (ref "IC4") (pin "3") (pinfunction "+IN_3") (pintype "input"))
      (node (ref "R4") (pin "2") (pinfunction "2_2") (pintype "passive"))
      (node (ref "R8") (pin "1") (pinfunction "1_1") (pintype "passive"))
    )
    (net (code "137") (name "Net-(IC4B-+IN)") (class "Default")
      (node (ref "C46") (pin "1") (pinfunction "1_1") (pintype "passive"))
      (node (ref "IC4") (pin "5") (pinfunction "+IN_5") (pintype "input"))
      (node (ref "R10") (pin "2") (pinfunction "2_2") (pintype "passive"))
      (node (ref "R12") (pin "1") (pinfunction "1_1") (pintype "passive"))
    )
    (net (code "138") (name "Net-(IC5-OSCI)") (class "Default")
      (node (ref "IC5") (pin "1") (pinfunction "OSCI_1") (pintype "input"))
      (node (ref "Q7") (pin "2") (pinfunction "2_2") (pintype "passive"))
    )
    (net (code "139") (name "Net-(IC5-OSCO)") (class "Default")
      (node (ref "IC5") (pin "2") (pinfunction "OSCO_2") (pintype "output"))
      (node (ref "Q7") (pin "1") (pinfunction "1_1") (pintype "passive"))
    )
    (net (code "140") (name "Net-(IC7-ITH)") (class "Default")
      (node (ref "IC7") (pin "2") (pinfunction "ITH_2") (pintype "input"))
      (node (ref "R27") (pin "2") (pinfunction "2_2") (pintype "passive"))
    )
    (net (code "141") (name "Net-(IC7-MODE)") (class "Default")
      (node (ref "C27") (pin "1") (pinfunction "1_1") (pintype "passive"))
      (node (ref "C28") (pin "1") (pinfunction "1_1") (pintype "passive"))
      (node (ref "C29") (pin "1") (pinfunction "1_1") (pintype "passive"))
      (node (ref "IC7") (pin "6") (pinfunction "VIN_6") (pintype "input"))
      (node (ref "IC7") (pin "8") (pinfunction "MODE_8") (pintype "input"))
      (node (ref "L5") (pin "2") (pinfunction "2_2") (pintype "passive"))
      (node (ref "R18") (pin "2") (pinfunction "2_2") (pintype "passive"))
    )
    (net (code "142") (name "Net-(IC7-PGATE)") (class "Default")
      (node (ref "IC7") (pin "5") (pinfunction "PGATE_5") (pintype "output"))
      (node (ref "Q11") (pin "1") (pinfunction "G_1") (pintype "passive"))
    )
    (net (code "143") (name "Net-(IC7-RUN{slash}SS)") (class "Default")
      (node (ref "C35") (pin "1") (pinfunction "1_1") (pintype "passive"))
      (node (ref "IC7") (pin "1") (pinfunction "RUN/SS_1") (pintype "input"))
    )
    (net (code "144") (name "Net-(IC7-SENSE)") (class "Default")
      (node (ref "C27") (pin "2") (pinfunction "2_2") (pintype "passive"))
      (node (ref "IC7") (pin "7") (pinfunction "SENSE_7") (pintype "input"))
      (node (ref "Q11") (pin "2") (pinfunction "S_2") (pintype "passive"))
      (node (ref "R18") (pin "1") (pinfunction "1_1") (pintype "passive"))
    )
    (net (code "145") (name "Net-(IC7-VFB)") (class "Default")
      (node (ref "C33") (pin "1") (pinfunction "1_1") (pintype "passive"))
      (node (ref "IC7") (pin "3") (pinfunction "VFB_3") (pintype "input"))
      (node (ref "R28") (pin "1") (pinfunction "1_1") (pintype "passive"))
      (node (ref "R37") (pin "2") (pinfunction "2_2") (pintype "passive"))
      (node (ref "R83") (pin "2") (pinfunction "2_2") (pintype "passive"))
    )
    (net (code "146") (name "Net-(IC8-EN_A)") (class "Default")
      (node (ref "C40") (pin "1") (pinfunction "1_1") (pintype "passive"))
      (node (ref "IC8") (pin "25") (pinfunction "EN_A_25") (pintype "input"))
      (node (ref "R36") (pin "4") (pinfunction "1_4") (pintype "passive"))
    )
    (net (code "147") (name "Net-(IC8-EN_B)") (class "Default")
      (node (ref "C43") (pin "1") (pinfunction "1_1") (pintype "passive"))
      (node (ref "IC8") (pin "16") (pinfunction "EN_B_16") (pintype "input"))
      (node (ref "R36") (pin "3") (pinfunction "1_3") (pintype "passive"))
    )
    (net (code "148") (name "Net-(IC8-RCA)") (class "Default")
      (node (ref "C55") (pin "1") (pinfunction "1_1") (pintype "passive"))
      (node (ref "IC8") (pin "30") (pinfunction "RCA_30") (pintype "input"))
      (node (ref "R36") (pin "2") (pinfunction "1_2") (pintype "passive"))
    )
    (net (code "149") (name "Net-(IC8-RCB)") (class "Default")
      (node (ref "C54") (pin "1") (pinfunction "1_1") (pintype "passive"))
      (node (ref "IC8") (pin "11") (pinfunction "RCB_11") (pintype "input"))
      (node (ref "R36") (pin "1") (pinfunction "1_1") (pintype "passive"))
    )
    (net (code "150") (name "Net-(IC8-SENSE_A)") (class "Default")
      (node (ref "IC8") (pin "29") (pinfunction "SENSE_A_29") (pintype "input"))
      (node (ref "R40") (pin "2") (pinfunction "2_2") (pintype "passive"))
    )
    (net (code "151") (name "Net-(IC8-SENSE_B)") (class "Default")
      (node (ref "IC8") (pin "12") (pinfunction "SENSE_B_12") (pintype "input"))
      (node (ref "R35") (pin "2") (pinfunction "2_2") (pintype "passive"))
    )
    (net (code "152") (name "Net-(IC8-VCP)") (class "Default")
      (node (ref "C31") (pin "2") (pinfunction "2_2") (pintype "passive"))
      (node (ref "IC8") (pin "24") (pinfunction "VCP_24") (pintype "input"))
    )
    (net (code "153") (name "Net-(IC8-VREF_A)") (class "Default")
      (node (ref "IC8") (pin "15") (pinfunction "VREF_B_15") (pintype "input"))
      (node (ref "IC8") (pin "26") (pinfunction "VREF_A_26") (pintype "input"))
      (node (ref "R32") (pin "2") (pinfunction "2_2") (pintype "passive"))
      (node (ref "R7") (pin "5") (pinfunction "2_5") (pintype "passive"))
    )
    (net (code "154") (name "Net-(IC9-REF)") (class "Default")
      (node (ref "IC9") (pin "1") (pinfunction "REF_1") (pintype "input"))
      (node (ref "R44") (pin "1") (pinfunction "1_1") (pintype "passive"))
      (node (ref "R45") (pin "2") (pinfunction "2_2") (pintype "passive"))
    )
    (net (code "155") (name "Net-(IC11-VDD)") (class "Default")
      (node (ref "C23") (pin "1") (pinfunction "1_1") (pintype "passive"))
      (node (ref "IC11") (pin "5") (pinfunction "VDD_5") (pintype "input"))
      (node (ref "J10") (pin "2") (pinfunction "2_2") (pintype "passive"))
      (node (ref "R43") (pin "1") (pinfunction "1_1") (pintype "passive"))
    )
    (net (code "156") (name "Net-(IC12A-+IN)") (class "Default")
      (node (ref "C11") (pin "1") (pinfunction "1_1") (pintype "passive"))
      (node (ref "IC12") (pin "3") (pinfunction "+IN_3") (pintype "input"))
      (node (ref "R41") (pin "2") (pinfunction "2_2") (pintype "passive"))
      (node (ref "R5") (pin "1") (pinfunction "1_1") (pintype "passive"))
    )
    (net (code "157") (name "Net-(IC12B--IN)") (class "Default")
      (node (ref "IC12") (pin "6") (pinfunction "-IN_6") (pintype "input"))
      (node (ref "R58") (pin "1") (pinfunction "1_1") (pintype "passive"))
      (node (ref "R59") (pin "1") (pinfunction "1_1") (pintype "passive"))
    )
    (net (code "158") (name "Net-(IC12B-OUT)") (class "Default")
      (node (ref "IC12") (pin "7") (pinfunction "OUT_7") (pintype "output"))
      (node (ref "R58") (pin "2") (pinfunction "2_2") (pintype "passive"))
      (node (ref "R65") (pin "1") (pinfunction "1_1") (pintype "passive"))
    )
    (net (code "159") (name "Net-(IC13-WP)") (class "Default")
      (node (ref "IC13") (pin "7") (pinfunction "WP_7") (pintype "input"))
      (node (ref "R56") (pin "2") (pinfunction "2_2") (pintype "passive"))
      (node (ref "TP11") (pin "P$1") (pinfunction "TP_P$1") (pintype "passive"))
    )
    (net (code "160") (name "Net-(IC14-FB)") (class "Default")
      (node (ref "IC14") (pin "3") (pinfunction "FB_3") (pintype "input"))
      (node (ref "R47") (pin "1") (pinfunction "1_1") (pintype "passive"))
      (node (ref "R51") (pin "2") (pinfunction "2_2") (pintype "passive"))
      (node (ref "R65") (pin "2") (pinfunction "2_2") (pintype "passive"))
      (node (ref "R66") (pin "1") (pinfunction "1_1") (pintype "passive"))
    )
    (net (code "161") (name "Net-(IC14-IN)") (class "Default")
      (node (ref "C24") (pin "1") (pinfunction "1_1") (pintype "passive"))
      (node (ref "C49") (pin "1") (pinfunction "1_1") (pintype "passive"))
      (node (ref "IC14") (pin "5") (pinfunction "IN_5") (pintype "input"))
      (node (ref "L4") (pin "1") (pinfunction "1_1") (pintype "passive"))
      (node (ref "L6") (pin "2") (pinfunction "2_2") (pintype "passive"))
      (node (ref "R67") (pin "2") (pinfunction "2_2") (pintype "passive"))
    )
    (net (code "162") (name "Net-(IC14-SD{slash}SS)") (class "Default")
      (node (ref "IC14") (pin "4") (pinfunction "SD/SS_4") (pintype "input"))
      (node (ref "R13") (pin "2") (pinfunction "2_2") (pintype "passive"))
      (node (ref "R22") (pin "2") (pinfunction "2_2") (pintype "passive"))
      (node (ref "R67") (pin "1") (pinfunction "1_1") (pintype "passive"))
    )
    (net (code "163") (name "Net-(IC14-SW)") (class "Default")
      (node (ref "C50") (pin "1") (pinfunction "1_1") (pintype "passive"))
      (node (ref "IC14") (pin "1") (pinfunction "SW_1") (pintype "output"))
      (node (ref "L4") (pin "3") (pinfunction "2_3") (pintype "passive"))
    )
    (net (code "164") (name "Net-(IC15A-+IN)") (class "Default")
      (node (ref "C66") (pin "1") (pinfunction "1_1") (pintype "passive"))
      (node (ref "IC15") (pin "3") (pinfunction "+IN_3") (pintype "input"))
      (node (ref "R63") (pin "2") (pinfunction "2_2") (pintype "passive"))
      (node (ref "R77") (pin "2") (pinfunction "2_2") (pintype "passive"))
    )
    (net (code "165") (name "Net-(IC15B-+IN)") (class "Default")
      (node (ref "IC15") (pin "5") (pinfunction "+IN_5") (pintype "input"))
      (node (ref "R76") (pin "2") (pinfunction "2_2") (pintype "passive"))
      (node (ref "R77") (pin "1") (pinfunction "1_1") (pintype "passive"))
    )
    (net (code "166") (name "Net-(IC15C-V+)") (class "Default")
      (node (ref "C68") (pin "1") (pinfunction "1_1") (pintype "passive"))
      (node (ref "IC15") (pin "8") (pinfunction "V+_8") (pintype "input"))
      (node (ref "R70") (pin "1") (pinfunction "1_1") (pintype "passive"))
    )
    (net (code "167") (name "Net-(IC16A-+IN)") (class "Default")
      (node (ref "C75") (pin "1") (pinfunction "1_1") (pintype "passive"))
      (node (ref "IC16") (pin "3") (pinfunction "+IN_3") (pintype "input"))
      (node (ref "R78") (pin "1") (pinfunction "1_1") (pintype "passive"))
      (node (ref "R87") (pin "1") (pinfunction "1_1") (pintype "passive"))
    )
    (net (code "168") (name "Net-(IC16A--IN)") (class "Default")
      (node (ref "IC16") (pin "1") (pinfunction "OUT_1") (pintype "output"))
      (node (ref "IC16") (pin "2") (pinfunction "-IN_2") (pintype "input"))
      (node (ref "R92") (pin "1") (pinfunction "1_1") (pintype "passive"))
    )
    (net (code "169") (name "Net-(IC16B-+IN)") (class "Default")
      (node (ref "C76") (pin "1") (pinfunction "1_1") (pintype "passive"))
      (node (ref "IC16") (pin "5") (pinfunction "+IN_5") (pintype "input"))
      (node (ref "R89") (pin "1") (pinfunction "1_1") (pintype "passive"))
      (node (ref "R91") (pin "1") (pinfunction "1_1") (pintype "passive"))
    )
    (net (code "170") (name "Net-(IC16B--IN)") (class "Default")
      (node (ref "IC16") (pin "6") (pinfunction "-IN_6") (pintype "input"))
      (node (ref "IC16") (pin "7") (pinfunction "OUT_7") (pintype "output"))
      (node (ref "R93") (pin "1") (pinfunction "1_1") (pintype "passive"))
    )
    (net (code "171") (name "Net-(IC16C-V+)") (class "Default")
      (node (ref "C73") (pin "1") (pinfunction "1_1") (pintype "passive"))
      (node (ref "IC16") (pin "8") (pinfunction "V+_8") (pintype "input"))
      (node (ref "R60") (pin "1") (pinfunction "1_1") (pintype "passive"))
    )
    (net (code "172") (name "Net-(IC17--UNDERV)") (class "Default")
      (node (ref "IC17") (pin "23") (pinfunction "-UNDERV_23") (pintype "bidirectional"))
      (node (ref "R14") (pin "4") (pinfunction "1_4") (pintype "passive"))
    )
    (net (code "173") (name "Net-(IC17-C+)") (class "Default")
      (node (ref "C14") (pin "2") (pinfunction "2_2") (pintype "passive"))
      (node (ref "IC17") (pin "14") (pinfunction "C+_14") (pintype "input"))
    )
    (net (code "174") (name "Net-(IC17-C-)") (class "Default")
      (node (ref "C14") (pin "1") (pinfunction "1_1") (pintype "passive"))
      (node (ref "IC17") (pin "11") (pinfunction "C-_11") (pintype "input"))
    )
    (net (code "175") (name "Net-(IC17-CLKB)") (class "Default")
      (node (ref "IC17") (pin "18") (pinfunction "CLKB_18") (pintype "bidirectional"))
      (node (ref "J17") (pin "C3") (pinfunction "C3_C3") (pintype "bidirectional"))
    )
    (net (code "176") (name "Net-(IC17-CPO)") (class "Default")
      (node (ref "C22") (pin "2") (pinfunction "2_2") (pintype "passive"))
      (node (ref "IC17") (pin "15") (pinfunction "CPO_15") (pintype "bidirectional"))
    )
    (net (code "177") (name "Net-(IC17-NC{slash}-NO)") (class "Default")
      (node (ref "IC17") (pin "22") (pinfunction "NC/-NO_22") (pintype "bidirectional"))
      (node (ref "R23") (pin "2") (pinfunction "2_2") (pintype "passive"))
    )
    (net (code "178") (name "Net-(IC17-RSTB)") (class "Default")
      (node (ref "IC17") (pin "19") (pinfunction "RSTB_19") (pintype "bidirectional"))
      (node (ref "J17") (pin "C2") (pinfunction "C2_C2") (pintype "bidirectional"))
    )
    (net (code "179") (name "Net-(IC17-VCCB)") (class "Default")
      (node (ref "IC17") (pin "17") (pinfunction "VCCB_17") (pintype "bidirectional"))
      (node (ref "J17") (pin "C1") (pinfunction "C1_C1") (pintype "bidirectional"))
    )
    (net (code "180") (name "Net-(L4B-2)") (class "Default")
      (node (ref "C50") (pin "2") (pinfunction "2_2") (pintype "passive"))
      (node (ref "D10") (pin "A") (pinfunction "A_A") (pintype "passive"))
      (node (ref "L4") (pin "4") (pinfunction "2_4") (pintype "passive"))
    )
    (net (code "181") (name "Net-(Q1A-D)") (class "Default")
      (node (ref "Q1") (pin "6") (pinfunction "D_6") (pintype "passive"))
      (node (ref "R39") (pin "1") (pinfunction "1_1") (pintype "passive"))
    )
    (net (code "182") (name "Net-(Q3-Q2D1)") (class "Default")
      (node (ref "Q3") (pin "2") (pinfunction "Q2D1_2") (pintype "bidirectional"))
      (node (ref "Q3") (pin "3") (pinfunction "Q2D2_3") (pintype "bidirectional"))
      (node (ref "R48") (pin "1") (pinfunction "1_1") (pintype "passive"))
      (node (ref "R49") (pin "1") (pinfunction "1_1") (pintype "passive"))
    )
    (net (code "183") (name "Net-(Q3-Q2G)") (class "Default")
      (node (ref "Q3") (pin "6") (pinfunction "Q2G_6") (pintype "input"))
      (node (ref "R9") (pin "3") (pinfunction "1_3") (pintype "passive"))
    )
    (net (code "184") (name "Net-(Q4A-D)") (class "Default")
      (node (ref "Q4") (pin "6") (pinfunction "D_6") (pintype "passive"))
      (node (ref "R6") (pin "1") (pinfunction "1_1") (pintype "passive"))
    )
    (net (code "185") (name "Net-(Q4B-D)") (class "Default")
      (node (ref "Q4") (pin "3") (pinfunction "D_3") (pintype "passive"))
      (node (ref "R54") (pin "1") (pinfunction "1_1") (pintype "passive"))
    )
    (net (code "186") (name "Net-(Q5-Q1S)") (class "Default")
      (node (ref "Q5") (pin "1") (pinfunction "Q1S_1") (pintype "bidirectional"))
      (node (ref "R61") (pin "1") (pinfunction "1_1") (pintype "passive"))
    )
    (net (code "187") (name "Net-(Q5-Q2D1)") (class "Default")
      (node (ref "J1") (pin "4") (pinfunction "4_4") (pintype "passive"))
      (node (ref "Q5") (pin "2") (pinfunction "Q2D1_2") (pintype "bidirectional"))
      (node (ref "Q5") (pin "3") (pinfunction "Q2D2_3") (pintype "bidirectional"))
    )
    (net (code "188") (name "Net-(Q5-Q2G)") (class "Default")
      (node (ref "C63") (pin "2") (pinfunction "2_2") (pintype "passive"))
      (node (ref "Q5") (pin "6") (pinfunction "Q2G_6") (pintype "input"))
      (node (ref "R62") (pin "2") (pinfunction "2_2") (pintype "passive"))
    )
    (net (code "189") (name "Net-(Q6A-D)") (class "Default")
      (node (ref "Q6") (pin "3") (pinfunction "D_3") (pintype "passive"))
      (node (ref "Q6") (pin "6") (pinfunction "D_6") (pintype "passive"))
      (node (ref "Q6") (pin "P1") (pinfunction "D1_P1") (pintype "passive"))
      (node (ref "Q6") (pin "P2") (pinfunction "D1_P2") (pintype "passive"))
    )
    (net (code "190") (name "Net-(Q6A-G)") (class "Default")
      (node (ref "Q6") (pin "2") (pinfunction "G_2") (pintype "passive"))
      (node (ref "R52") (pin "1") (pinfunction "1_1") (pintype "passive"))
      (node (ref "R6") (pin "2") (pinfunction "2_2") (pintype "passive"))
    )
    (net (code "191") (name "Net-(Q6B-G)") (class "Default")
      (node (ref "Q6") (pin "5") (pinfunction "G_5") (pintype "passive"))
      (node (ref "R53") (pin "1") (pinfunction "1_1") (pintype "passive"))
      (node (ref "R54") (pin "2") (pinfunction "2_2") (pintype "passive"))
    )
    (net (code "192") (name "Net-(Q8A-D)") (class "Default")
      (node (ref "Q8") (pin "3") (pinfunction "D_3") (pintype "passive"))
      (node (ref "Q8") (pin "6") (pinfunction "D_6") (pintype "passive"))
      (node (ref "Q8") (pin "P1") (pinfunction "D1_P1") (pintype "passive"))
      (node (ref "Q8") (pin "P2") (pinfunction "D1_P2") (pintype "passive"))
    )
    (net (code "193") (name "Net-(Q8A-G)") (class "Default")
      (node (ref "Q8") (pin "2") (pinfunction "G_2") (pintype "passive"))
      (node (ref "R16") (pin "8") (pinfunction "2_8") (pintype "passive"))
      (node (ref "R20") (pin "1") (pinfunction "1_1") (pintype "passive"))
    )
    (net (code "194") (name "Net-(Q8B-G)") (class "Default")
      (node (ref "Q8") (pin "5") (pinfunction "G_5") (pintype "passive"))
      (node (ref "R16") (pin "7") (pinfunction "2_7") (pintype "passive"))
      (node (ref "R20") (pin "2") (pinfunction "1_2") (pintype "passive"))
    )
    (net (code "195") (name "Net-(Q9A-D)") (class "Default")
      (node (ref "Q9") (pin "3") (pinfunction "D_3") (pintype "passive"))
      (node (ref "Q9") (pin "6") (pinfunction "D_6") (pintype "passive"))
      (node (ref "Q9") (pin "P1") (pinfunction "D1_P1") (pintype "passive"))
      (node (ref "Q9") (pin "P2") (pinfunction "D1_P2") (pintype "passive"))
    )
    (net (code "196") (name "Net-(Q9A-G)") (class "Default")
      (node (ref "Q9") (pin "2") (pinfunction "G_2") (pintype "passive"))
      (node (ref "R15") (pin "1") (pinfunction "1_1") (pintype "passive"))
      (node (ref "R21") (pin "8") (pinfunction "2_8") (pintype "passive"))
    )
    (net (code "197") (name "Net-(Q9B-G)") (class "Default")
      (node (ref "Q9") (pin "5") (pinfunction "G_5") (pintype "passive"))
      (node (ref "R17") (pin "1") (pinfunction "1_1") (pintype "passive"))
    )
    (net (code "198") (name "Net-(Q10A-D)") (class "Default")
      (node (ref "Q10") (pin "6") (pinfunction "D_6") (pintype "passive"))
      (node (ref "R20") (pin "8") (pinfunction "2_8") (pintype "passive"))
    )
    (net (code "199") (name "Net-(Q10B-D)") (class "Default")
      (node (ref "Q10") (pin "3") (pinfunction "D_3") (pintype "passive"))
      (node (ref "R20") (pin "6") (pinfunction "2_6") (pintype "passive"))
    )
    (net (code "200") (name "Net-(Q12A-D)") (class "Default")
      (node (ref "C41") (pin "1") (pinfunction "1_1") (pintype "passive"))
      (node (ref "Q12") (pin "5") (pinfunction "G_5") (pintype "passive"))
      (node (ref "Q12") (pin "6") (pinfunction "D_6") (pintype "passive"))
      (node (ref "R19") (pin "1") (pinfunction "1_1") (pintype "passive"))
    )
    (net (code "201") (name "Net-(Q12B-D)") (class "Default")
      (node (ref "Q12") (pin "3") (pinfunction "D_3") (pintype "passive"))
      (node (ref "R21") (pin "1") (pinfunction "1_1") (pintype "passive"))
    )
    (net (code "202") (name "Net-(Q13A-D)") (class "Default")
      (node (ref "Q13") (pin "6") (pinfunction "D_6") (pintype "passive"))
      (node (ref "R21") (pin "2") (pinfunction "1_2") (pintype "passive"))
    )
    (net (code "203") (name "Net-(Q13B-D)") (class "Default")
      (node (ref "Q13") (pin "3") (pinfunction "D_3") (pintype "passive"))
      (node (ref "R21") (pin "4") (pinfunction "1_4") (pintype "passive"))
    )
    (net (code "204") (name "Net-(Q14A-D)") (class "Default")
      (node (ref "Q14") (pin "3") (pinfunction "D_3") (pintype "passive"))
      (node (ref "Q14") (pin "6") (pinfunction "D_6") (pintype "passive"))
      (node (ref "Q14") (pin "P1") (pinfunction "D1_P1") (pintype "passive"))
      (node (ref "Q14") (pin "P2") (pinfunction "D1_P2") (pintype "passive"))
    )
    (net (code "205") (name "Net-(Q14A-G)") (class "Default")
      (node (ref "Q14") (pin "2") (pinfunction "G_2") (pintype "passive"))
      (node (ref "R16") (pin "6") (pinfunction "2_6") (pintype "passive"))
      (node (ref "R20") (pin "3") (pinfunction "1_3") (pintype "passive"))
    )
    (net (code "206") (name "Net-(Q14B-G)") (class "Default")
      (node (ref "Q14") (pin "5") (pinfunction "G_5") (pintype "passive"))
      (node (ref "R16") (pin "5") (pinfunction "2_5") (pintype "passive"))
      (node (ref "R20") (pin "4") (pinfunction "1_4") (pintype "passive"))
    )
    (net (code "207") (name "Net-(Q15A-D)") (class "Default")
      (node (ref "Q15") (pin "3") (pinfunction "D_3") (pintype "passive"))
      (node (ref "Q15") (pin "6") (pinfunction "D_6") (pintype "passive"))
      (node (ref "Q15") (pin "P1") (pinfunction "D1_P1") (pintype "passive"))
      (node (ref "Q15") (pin "P2") (pinfunction "D1_P2") (pintype "passive"))
    )
    (net (code "208") (name "Net-(Q15A-G)") (class "Default")
      (node (ref "Q15") (pin "2") (pinfunction "G_2") (pintype "passive"))
      (node (ref "R21") (pin "6") (pinfunction "2_6") (pintype "passive"))
      (node (ref "R29") (pin "1") (pinfunction "1_1") (pintype "passive"))
    )
    (net (code "209") (name "Net-(Q15B-G)") (class "Default")
      (node (ref "Q15") (pin "5") (pinfunction "G_5") (pintype "passive"))
      (node (ref "R21") (pin "5") (pinfunction "2_5") (pintype "passive"))
      (node (ref "R31") (pin "1") (pinfunction "1_1") (pintype "passive"))
    )
    (net (code "210") (name "Net-(Q16A-D)") (class "Default")
      (node (ref "Q16") (pin "6") (pinfunction "D_6") (pintype "passive"))
      (node (ref "R21") (pin "3") (pinfunction "1_3") (pintype "passive"))
    )
    (net (code "211") (name "Net-(Q16A-G)") (class "Default")
      (node (ref "C47") (pin "1") (pinfunction "1_1") (pintype "passive"))
      (node (ref "Q16") (pin "2") (pinfunction "G_2") (pintype "passive"))
      (node (ref "Q16") (pin "3") (pinfunction "D_3") (pintype "passive"))
      (node (ref "R30") (pin "1") (pinfunction "1_1") (pintype "passive"))
    )
    (net (code "212") (name "Net-(Q18A-D)") (class "Default")
      (node (ref "Q18") (pin "6") (pinfunction "D_6") (pintype "passive"))
      (node (ref "R20") (pin "7") (pinfunction "2_7") (pintype "passive"))
    )
    (net (code "213") (name "Net-(Q18B-D)") (class "Default")
      (node (ref "Q18") (pin "3") (pinfunction "D_3") (pintype "passive"))
      (node (ref "R20") (pin "5") (pinfunction "2_5") (pintype "passive"))
    )
    (net (code "214") (name "Net-(Q22A-G)") (class "Default")
      (node (ref "C62") (pin "2") (pinfunction "2_2") (pintype "passive"))
      (node (ref "Q22") (pin "2") (pinfunction "G_2") (pintype "passive"))
      (node (ref "Q23") (pin "3") (pinfunction "D_3") (pintype "passive"))
      (node (ref "R80") (pin "2") (pinfunction "2_2") (pintype "passive"))
    )
    (net (code "215") (name "Net-(Q22A-S)") (class "Default")
      (node (ref "C62") (pin "1") (pinfunction "1_1") (pintype "passive"))
      (node (ref "C72") (pin "1") (pinfunction "1_1") (pintype "passive"))
      (node (ref "Q22") (pin "1") (pinfunction "S_1") (pintype "passive"))
      (node (ref "Q22") (pin "4") (pinfunction "S_4") (pintype "passive"))
      (node (ref "R80") (pin "1") (pinfunction "1_1") (pintype "passive"))
      (node (ref "R88") (pin "1") (pinfunction "1_1") (pintype "passive"))
    )
    (net (code "216") (name "Net-(Q22B-G)") (class "Default")
      (node (ref "C72") (pin "2") (pinfunction "2_2") (pintype "passive"))
      (node (ref "Q22") (pin "5") (pinfunction "G_5") (pintype "passive"))
      (node (ref "Q23") (pin "6") (pinfunction "D_6") (pintype "passive"))
      (node (ref "R88") (pin "2") (pinfunction "2_2") (pintype "passive"))
    )
    (net (code "217") (name "Net-(Q23A-S)") (class "Default")
      (node (ref "Q23") (pin "1") (pinfunction "S_1") (pintype "passive"))
      (node (ref "R90") (pin "2") (pinfunction "2_2") (pintype "passive"))
    )
    (net (code "218") (name "Net-(Q23B-S)") (class "Default")
      (node (ref "Q23") (pin "4") (pinfunction "S_4") (pintype "passive"))
      (node (ref "R79") (pin "2") (pinfunction "2_2") (pintype "passive"))
    )
    (net (code "219") (name "Net-(R2A-2)") (class "Default")
      (node (ref "J1") (pin "3") (pinfunction "3_3") (pintype "passive"))
      (node (ref "R2") (pin "8") (pinfunction "2_8") (pintype "passive"))
    )
    (net (code "220") (name "Net-(R2C-2)") (class "Default")
      (node (ref "J1") (pin "2") (pinfunction "2_2") (pintype "passive"))
      (node (ref "R2") (pin "6") (pinfunction "2_6") (pintype "passive"))
    )
    (net (code "221") (name "Net-(R14C-2)") (class "Default")
      (node (ref "R14") (pin "5") (pinfunction "2_5") (pintype "passive"))
      (node (ref "R14") (pin "6") (pinfunction "2_6") (pintype "passive"))
    )
    (net (code "222") (name "Net-(R25C-1)") (class "Default")
      (node (ref "R25") (pin "3") (pinfunction "1_3") (pintype "passive"))
      (node (ref "R25") (pin "5") (pinfunction "2_5") (pintype "passive"))
    )
    (net (code "223") (name "Net-(R64-Pad1)") (class "Default")
      (node (ref "R64") (pin "1") (pinfunction "1_1") (pintype "passive"))
      (node (ref "R76") (pin "1") (pinfunction "1_1") (pintype "passive"))
    )
    (net (code "224") (name "PGND") (class "Default")
      (node (ref "C12") (pin "2") (pinfunction "2_2") (pintype "passive"))
      (node (ref "C38") (pin "2") (pinfunction "2_2") (pintype "passive"))
      (node (ref "C39") (pin "2") (pinfunction "2_2") (pintype "passive"))
      (node (ref "C40") (pin "2") (pinfunction "2_2") (pintype "passive"))
      (node (ref "C43") (pin "2") (pinfunction "2_2") (pintype "passive"))
      (node (ref "C44") (pin "2") (pinfunction "2_2") (pintype "passive"))
      (node (ref "C52") (pin "2") (pinfunction "2_2") (pintype "passive"))
      (node (ref "C53") (pin "2") (pinfunction "2_2") (pintype "passive"))
      (node (ref "C54") (pin "2") (pinfunction "2_2") (pintype "passive"))
      (node (ref "C55") (pin "2") (pinfunction "2_2") (pintype "passive"))
      (node (ref "D6") (pin "A") (pinfunction "A_A") (pintype "passive"))
      (node (ref "D7") (pin "1") (pinfunction "A_1") (pintype "passive"))
      (node (ref "IC8") (pin "1") (pinfunction "GND1_1") (pintype "input"))
      (node (ref "IC8") (pin "2") (pinfunction "GND2_2") (pintype "input"))
      (node (ref "IC8") (pin "21") (pinfunction "GND21_21") (pintype "input"))
      (node (ref "IC8") (pin "3") (pinfunction "GND3_3") (pintype "input"))
      (node (ref "IC8") (pin "4") (pinfunction "GND4_4") (pintype "input"))
      (node (ref "IC8") (pin "5") (pinfunction "GND5_5") (pintype "input"))
      (node (ref "IC8") (pin "6") (pinfunction "GND6_6") (pintype "input"))
      (node (ref "IC8") (pin "7") (pinfunction "GND7_7") (pintype "input"))
      (node (ref "IC8") (pin "8") (pinfunction "GND8_8") (pintype "input"))
      (node (ref "IC8") (pin "G") (pinfunction "GNEXP_G") (pintype "input"))
      (node (ref "J14") (pin "5") (pinfunction "5_5") (pintype "passive"))
      (node (ref "J15") (pin "5") (pinfunction "5_5") (pintype "passive"))
      (node (ref "L2") (pin "1") (pinfunction "1_1") (pintype "passive"))
      (node (ref "Q3") (pin "1") (pinfunction "Q1S_1") (pintype "bidirectional"))
      (node (ref "R26") (pin "2") (pinfunction "1_2") (pintype "passive"))
      (node (ref "R26") (pin "4") (pinfunction "1_4") (pintype "passive"))
      (node (ref "R32") (pin "1") (pinfunction "1_1") (pintype "passive"))
      (node (ref "R35") (pin "1") (pinfunction "1_1") (pintype "passive"))
      (node (ref "R36") (pin "7") (pinfunction "2_7") (pintype "passive"))
      (node (ref "R36") (pin "8") (pinfunction "2_8") (pintype "passive"))
      (node (ref "R38") (pin "1") (pinfunction "1_1") (pintype "passive"))
      (node (ref "R38") (pin "2") (pinfunction "1_2") (pintype "passive"))
      (node (ref "R38") (pin "3") (pinfunction "1_3") (pintype "passive"))
      (node (ref "R38") (pin "4") (pinfunction "1_4") (pintype "passive"))
      (node (ref "R40") (pin "1") (pinfunction "1_1") (pintype "passive"))
      (node (ref "R50") (pin "5") (pinfunction "2_5") (pintype "passive"))
      (node (ref "R50") (pin "6") (pinfunction "2_6") (pintype "passive"))
      (node (ref "R9") (pin "2") (pinfunction "1_2") (pintype "passive"))
    )
    (net (code "225") (name "VACT") (class "Default")
      (node (ref "C37") (pin "1") (pinfunction "1_1") (pintype "passive"))
      (node (ref "C38") (pin "1") (pinfunction "1_1") (pintype "passive"))
      (node (ref "C39") (pin "1") (pinfunction "1_1") (pintype "passive"))
      (node (ref "D5") (pin "1") (pinfunction "A_1") (pintype "passive"))
      (node (ref "D6") (pin "C") (pinfunction "C_C") (pintype "passive"))
      (node (ref "IC8") (pin "20") (pinfunction "VS_B_20") (pintype "input"))
      (node (ref "IC8") (pin "22") (pinfunction "VS_A_22") (pintype "input"))
      (node (ref "J2") (pin "13") (pinfunction "13_13") (pintype "passive"))
      (node (ref "Q14") (pin "4") (pinfunction "S_4") (pintype "passive"))
      (node (ref "Q8") (pin "4") (pinfunction "S_4") (pintype "passive"))
      (node (ref "R16") (pin "2") (pinfunction "1_2") (pintype "passive"))
      (node (ref "R16") (pin "4") (pinfunction "1_4") (pintype "passive"))
      (node (ref "R39") (pin "2") (pinfunction "2_2") (pintype "passive"))
      (node (ref "R7") (pin "3") (pinfunction "1_3") (pintype "passive"))
      (node (ref "TP10") (pin "P$1") (pinfunction "TP_P$1") (pintype "passive"))
    )
    (net (code "226") (name "VBAT") (class "Default")
      (node (ref "C61") (pin "+") (pinfunction "+_+") (pintype "passive"))
      (node (ref "J7") (pin "7") (pinfunction "7_7") (pintype "passive"))
      (node (ref "J8") (pin "10") (pinfunction "10_10") (pintype "passive"))
      (node (ref "L5") (pin "1") (pinfunction "1_1") (pintype "passive"))
      (node (ref "Q15") (pin "4") (pinfunction "S_4") (pintype "passive"))
      (node (ref "Q22") (pin "6") (pinfunction "D_6") (pintype "passive"))
      (node (ref "Q22") (pin "P1") (pinfunction "D1_P1") (pintype "passive"))
      (node (ref "Q3") (pin "4") (pinfunction "Q2S_4") (pintype "bidirectional"))
      (node (ref "Q9") (pin "4") (pinfunction "S_4") (pintype "passive"))
      (node (ref "R17") (pin "2") (pinfunction "2_2") (pintype "passive"))
      (node (ref "R31") (pin "2") (pinfunction "2_2") (pintype "passive"))
      (node (ref "R63") (pin "1") (pinfunction "1_1") (pintype "passive"))
      (node (ref "R89") (pin "2") (pinfunction "2_2") (pintype "passive"))
      (node (ref "R9") (pin "6") (pinfunction "2_6") (pintype "passive"))
      (node (ref "TP2") (pin "P$1") (pinfunction "TP_P$1") (pintype "passive"))
    )
    (net (code "227") (name "unconnected-(IC5-CLKOUT-Pad13)") (class "Default")
      (node (ref "IC5") (pin "13") (pinfunction "CLKOUT_13") (pintype "open_collector"))
    )
    (net (code "228") (name "unconnected-(IC5-TEST-Pad4)") (class "Default")
      (node (ref "IC5") (pin "4") (pinfunction "TEST_4") (pintype "no_connect"))
    )
    (net (code "229") (name "unconnected-(IC6-OS-Pad3)") (class "Default")
      (node (ref "IC6") (pin "3") (pinfunction "OS_3") (pintype "output"))
    )
    (net (code "230") (name "unconnected-(IC17-NC-Pad16)") (class "Default")
      (node (ref "IC17") (pin "16") (pinfunction "NC_16") (pintype "bidirectional"))
    )
    (net (code "231") (name "unconnected-(J2-Pad11)") (class "Default")
      (node (ref "J2") (pin "11") (pinfunction "11_11") (pintype "passive"))
    )
    (net (code "232") (name "unconnected-(J17-PadC4)") (class "Default")
      (node (ref "J17") (pin "C4") (pinfunction "C4_C4") (pintype "bidirectional"))
    )
    (net (code "233") (name "unconnected-(J17-PadC6)") (class "Default")
      (node (ref "J17") (pin "C6") (pinfunction "C6_C6") (pintype "bidirectional"))
    )
    (net (code "234") (name "unconnected-(J17-PadC8)") (class "Default")
      (node (ref "J17") (pin "C8") (pinfunction "C8_C8") (pintype "bidirectional"))
    )
    (net (code "235") (name "unconnected-(R21B-2-Pad7)") (class "Default")
      (node (ref "R21") (pin "7") (pinfunction "2_7") (pintype "passive"))
    )
  )
)
